# USB3_0.net
KiCad netlist of a schematic drawn in Altium Designer
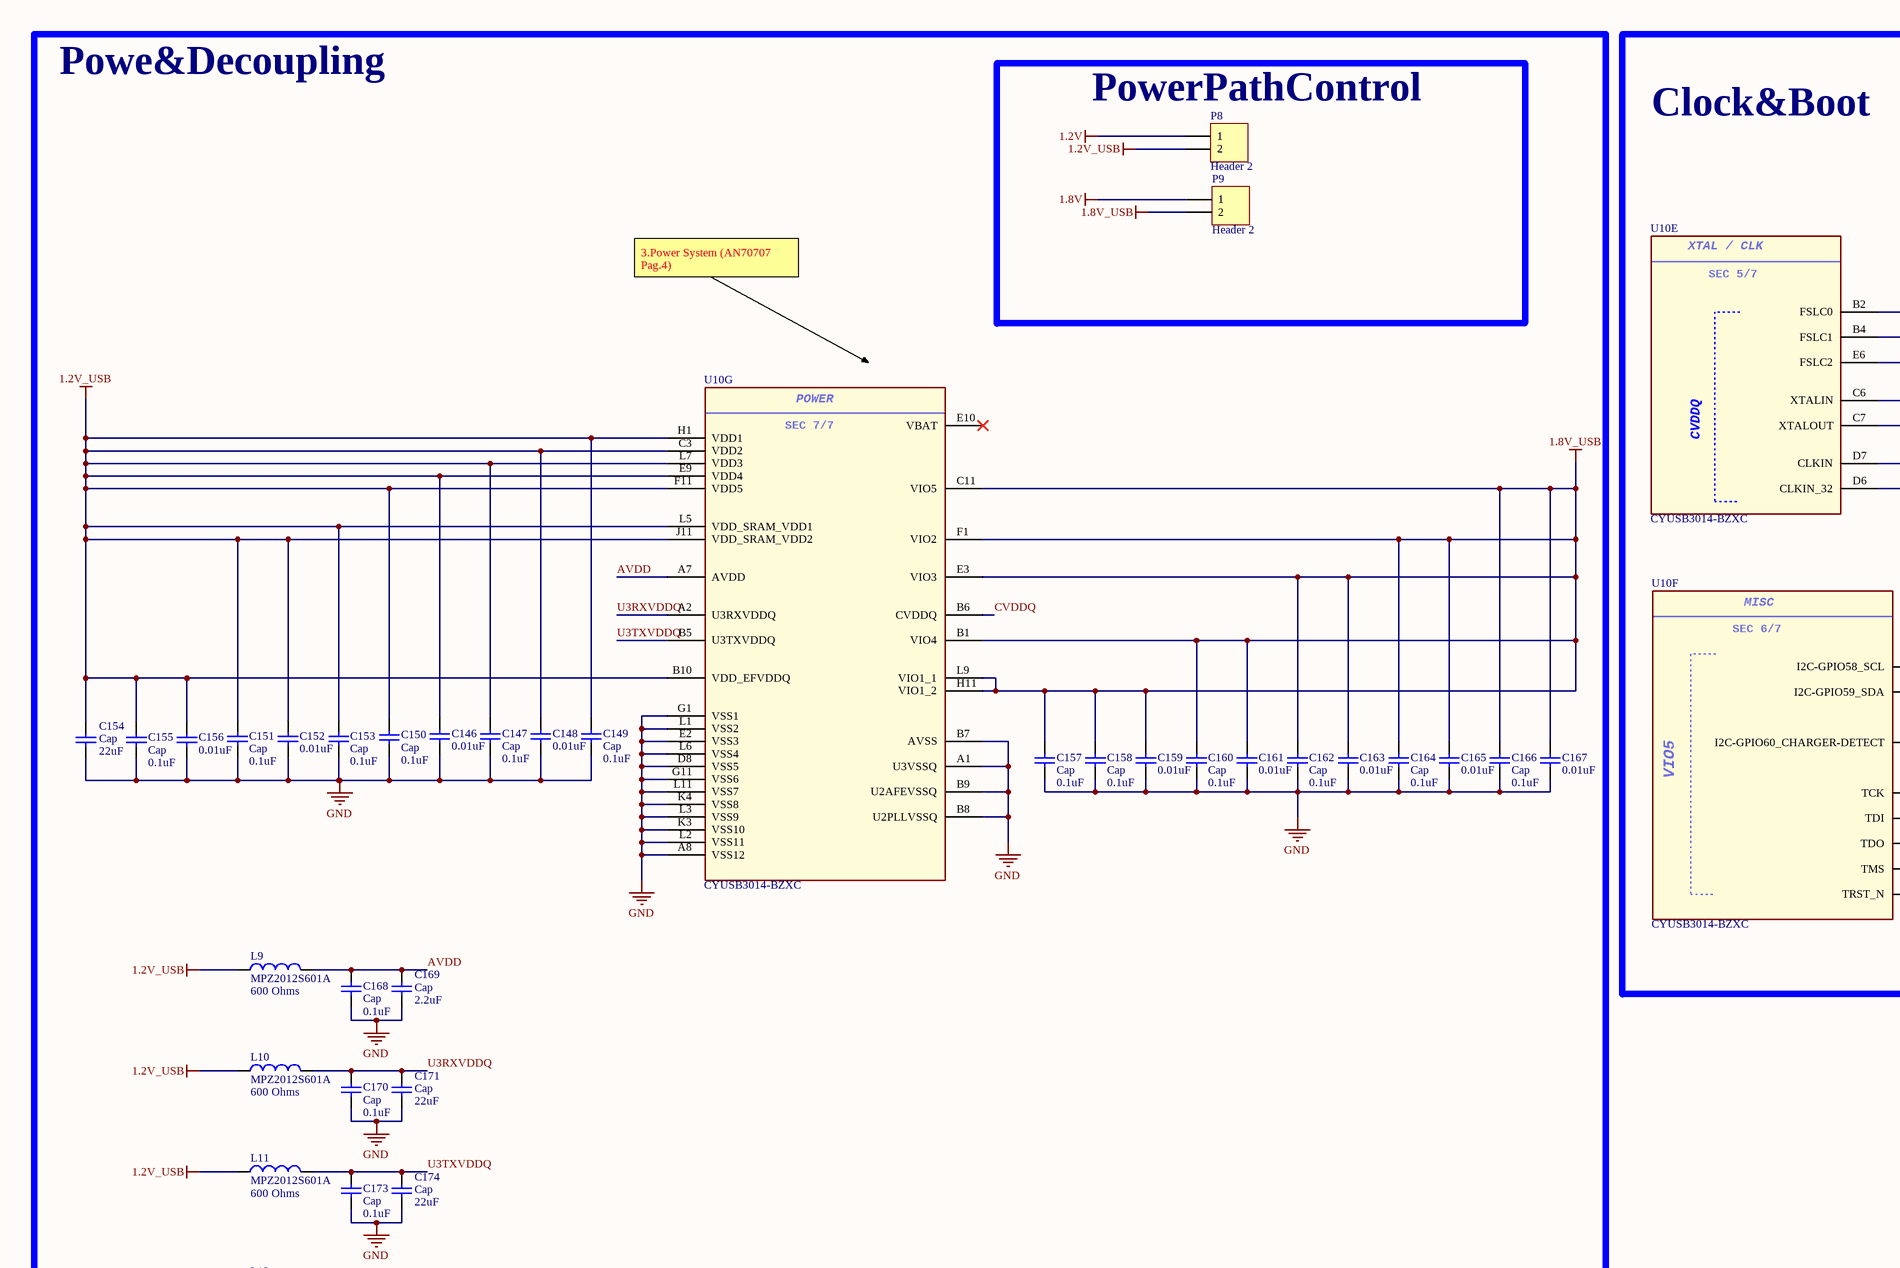
[diagram p0: USB3.0.SchDoc, top left]
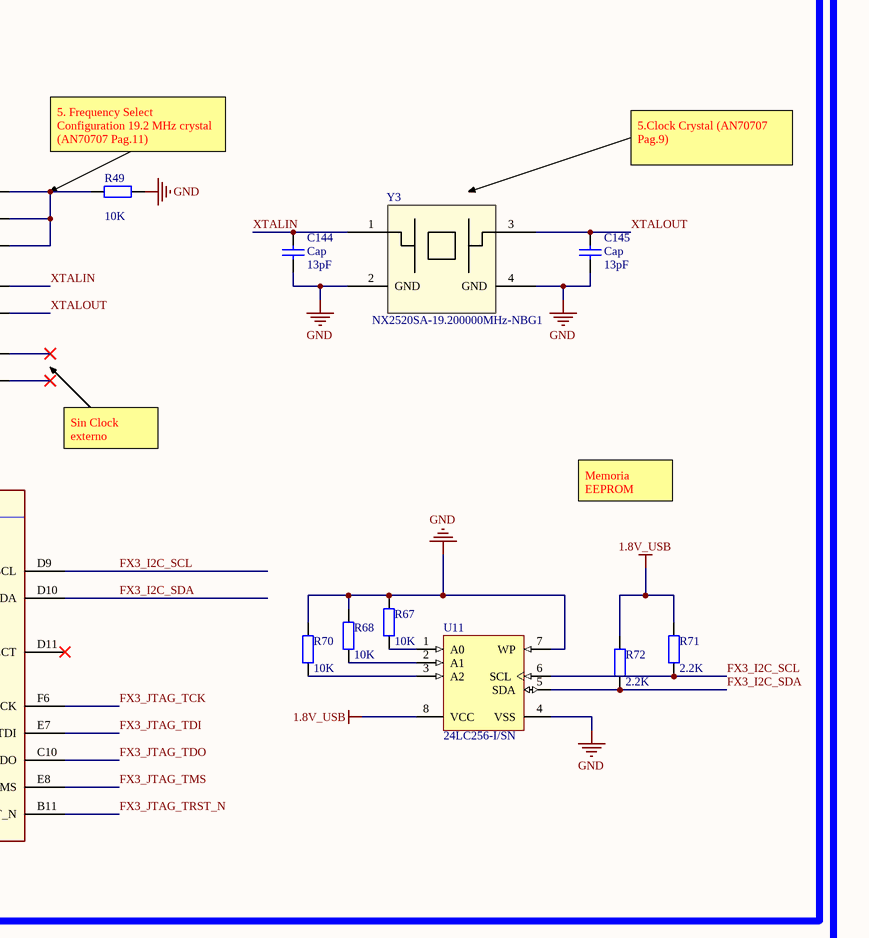
[diagram p1: USB3.0.SchDoc, top middle]
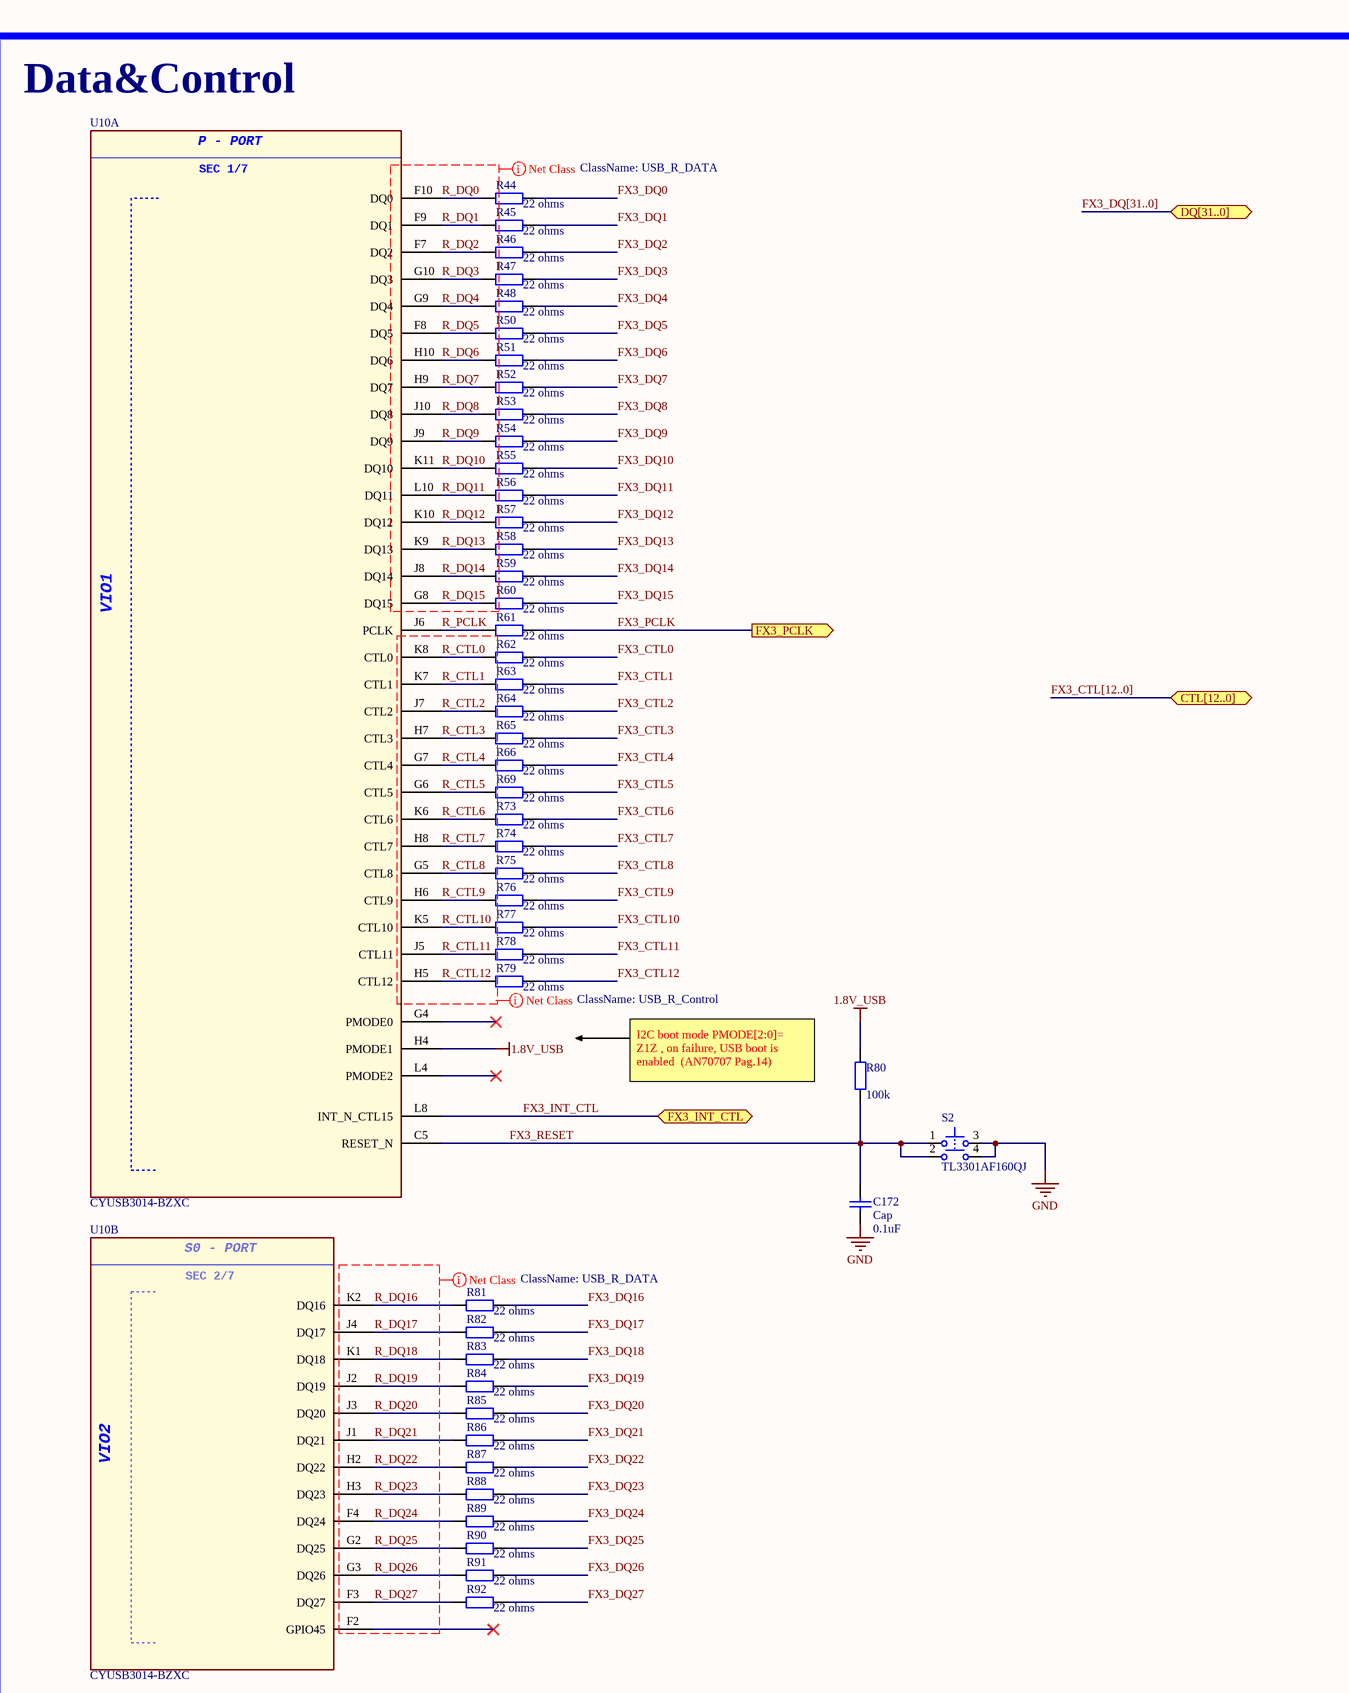
[diagram p2: USB3.0.SchDoc, top right]
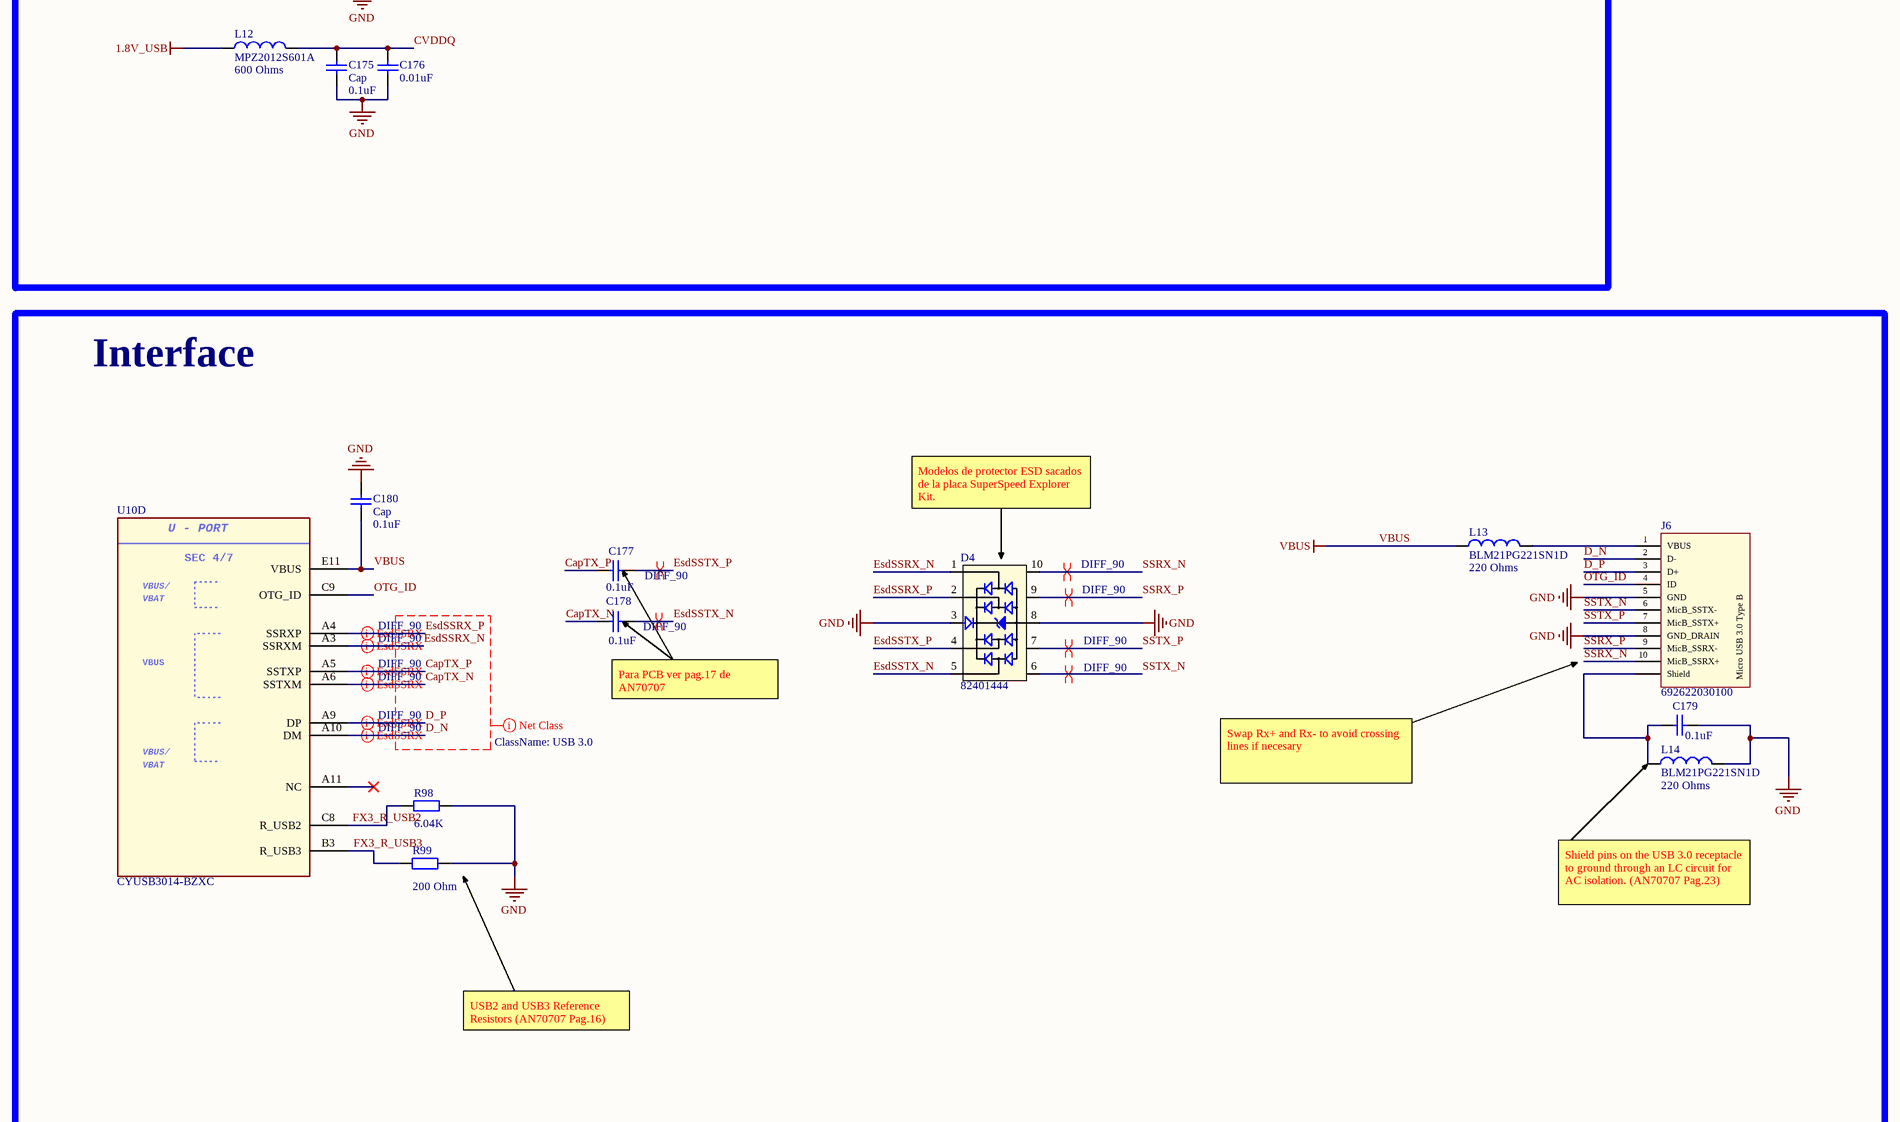
[diagram p3: USB3.0.SchDoc, bottom left]
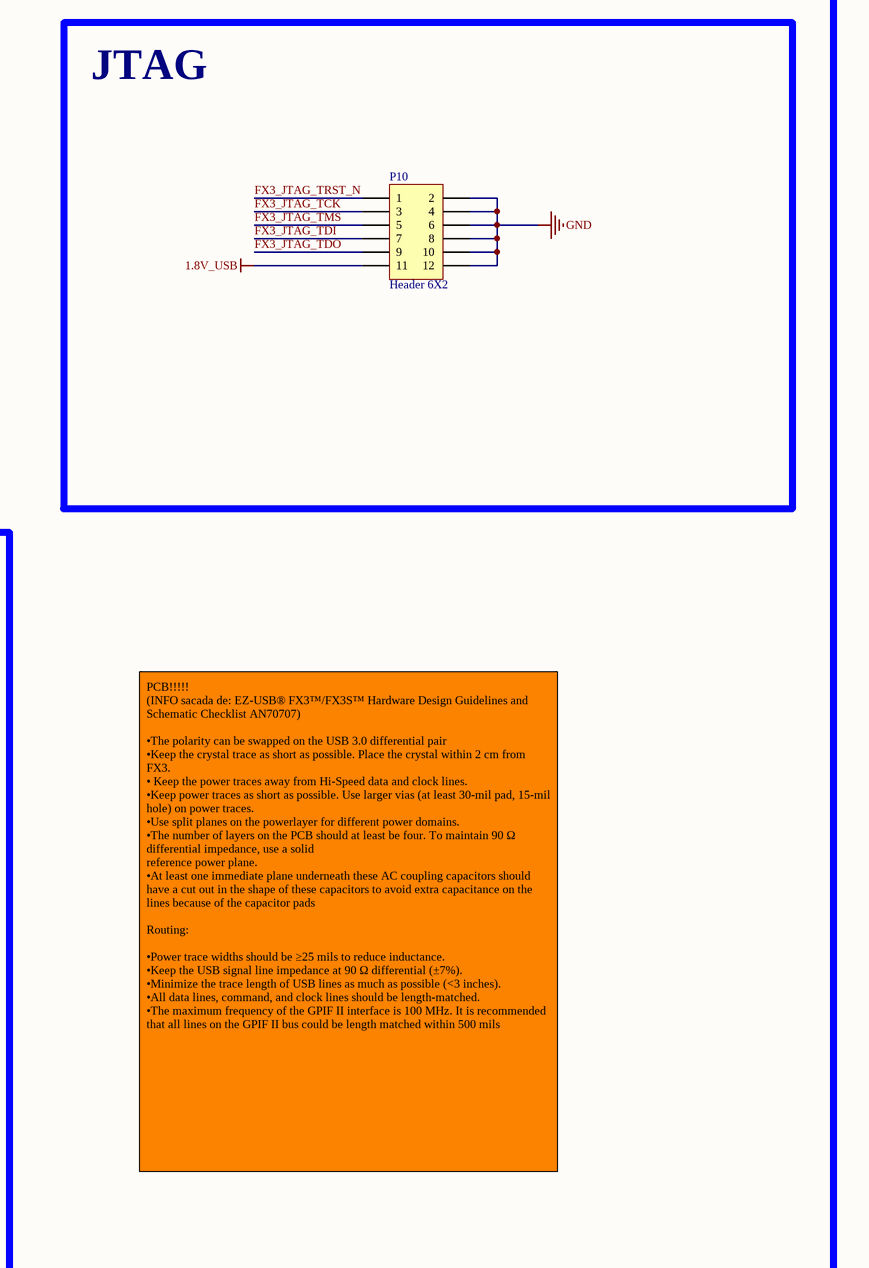
[diagram p4: USB3.0.SchDoc, bottom middle]
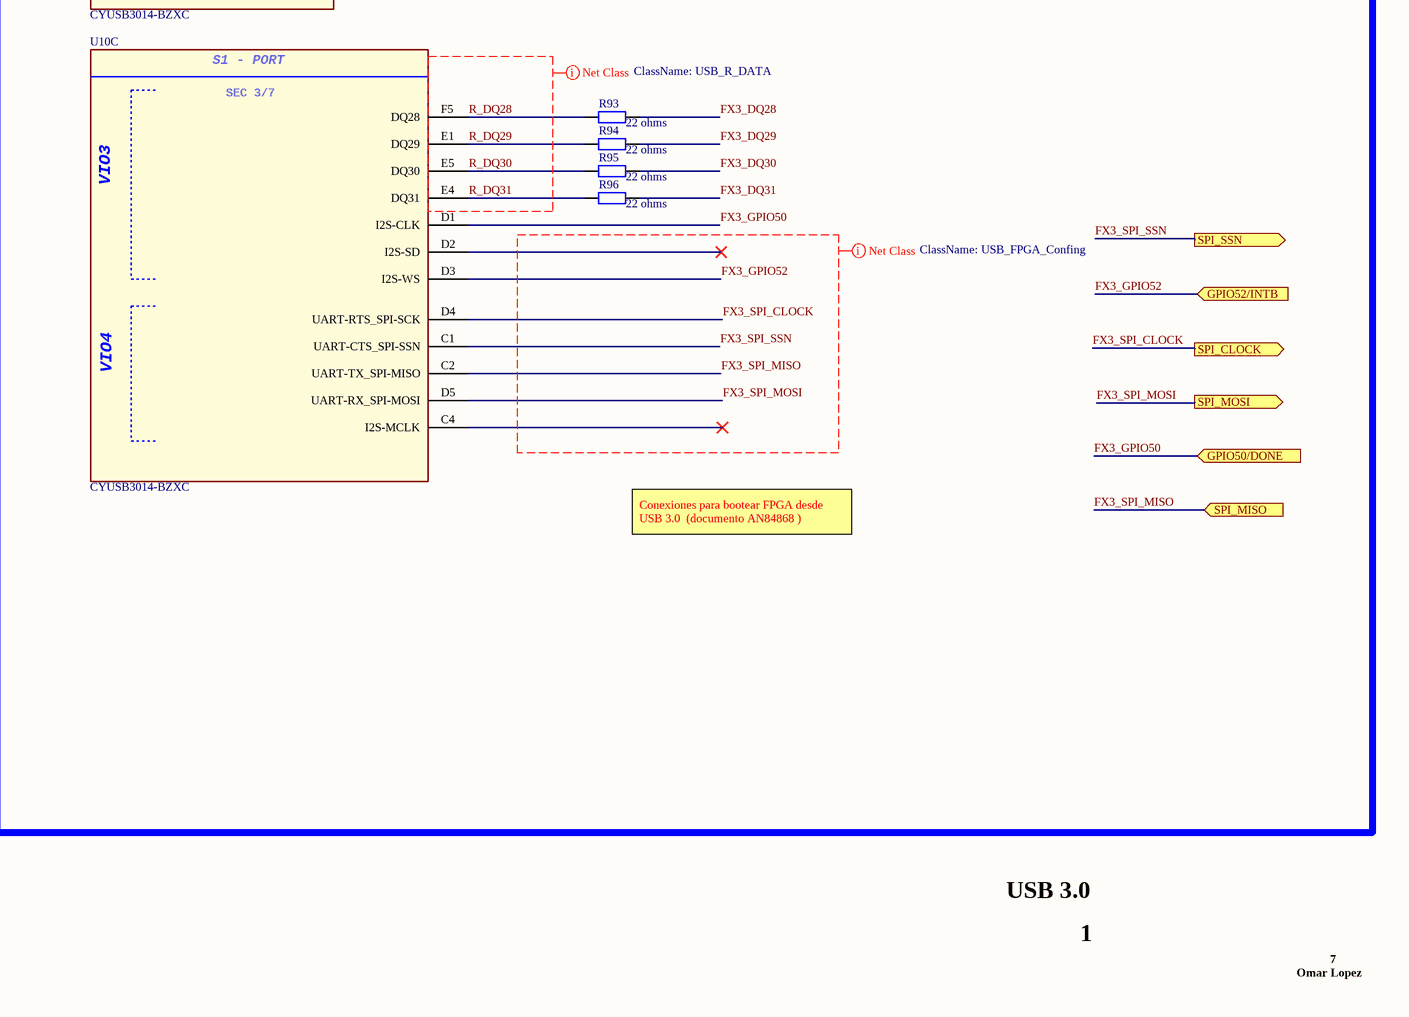
[diagram p5: USB3.0.SchDoc, bottom right]

(export (version "E")
  (design (tool "Eeschema 10.0.6"))
  (components
    (comp (ref "C144")
      (value "Cap")
      (footprint "MurataCapacitor:GRM0402MurataCap")
      (description "Capacitor")
      (fields
        (field (name "ALTIUM_VALUE") "13pF")
        (field (name "MANUFACTURER") "Murata")
        (field (name "TOLERANCE") "2%")
      )
      (libsource (lib "Miscellaneous Devices") (part "Cap"))
    )
    (comp (ref "C145")
      (value "Cap")
      (footprint "MurataCapacitor:GRM0402MurataCap")
      (description "Capacitor")
      (fields
        (field (name "ALTIUM_VALUE") "13pF")
        (field (name "MANUFACTURER") "Murata")
        (field (name "TOLERANCE") "2%")
      )
      (libsource (lib "Miscellaneous Devices") (part "Cap"))
    )
    (comp (ref "C146")
      (value "0.01uF")
      (footprint "MurataCapacitor:GRM0402MurataCap")
      (description "Capacitor")
      (fields (field (name "MANUFACTURER") "Murata") (field (name "TOLERANCE") "10%"))
      (libsource (lib "Miscellaneous Devices") (part "Cap"))
    )
    (comp (ref "C147")
      (value "Cap")
      (footprint "MurataCapacitor:GRM0402MurataCap")
      (description "Capacitor")
      (fields
        (field (name "ALTIUM_VALUE") "0.1uF")
        (field (name "MANUFACTURER") "Murata")
        (field (name "TOLERANCE") "10%")
      )
      (libsource (lib "Miscellaneous Devices") (part "Cap"))
    )
    (comp (ref "C148")
      (value "0.01uF")
      (footprint "MurataCapacitor:GRM0402MurataCap")
      (description "Capacitor")
      (fields (field (name "MANUFACTURER") "Murata") (field (name "TOLERANCE") "10%"))
      (libsource (lib "Miscellaneous Devices") (part "Cap"))
    )
    (comp (ref "C149")
      (value "Cap")
      (footprint "MurataCapacitor:GRM0402MurataCap")
      (description "Capacitor")
      (fields
        (field (name "ALTIUM_VALUE") "0.1uF")
        (field (name "MANUFACTURER") "Murata")
        (field (name "TOLERANCE") "10%")
      )
      (libsource (lib "Miscellaneous Devices") (part "Cap"))
    )
    (comp (ref "C150")
      (value "Cap")
      (footprint "MurataCapacitor:GRM0402MurataCap")
      (description "Capacitor")
      (fields
        (field (name "ALTIUM_VALUE") "0.1uF")
        (field (name "MANUFACTURER") "Murata")
        (field (name "TOLERANCE") "10%")
      )
      (libsource (lib "Miscellaneous Devices") (part "Cap"))
    )
    (comp (ref "C151")
      (value "Cap")
      (footprint "MurataCapacitor:GRM0402MurataCap")
      (description "Capacitor")
      (fields
        (field (name "ALTIUM_VALUE") "0.1uF")
        (field (name "MANUFACTURER") "Murata")
        (field (name "TOLERANCE") "10%")
      )
      (libsource (lib "Miscellaneous Devices") (part "Cap"))
    )
    (comp (ref "C152")
      (value "0.01uF")
      (footprint "MurataCapacitor:GRM0402MurataCap")
      (description "Capacitor")
      (fields (field (name "MANUFACTURER") "Murata") (field (name "TOLERANCE") "10%"))
      (libsource (lib "Miscellaneous Devices") (part "Cap"))
    )
    (comp (ref "C153")
      (value "Cap")
      (footprint "MurataCapacitor:GRM0402MurataCap")
      (description "Capacitor")
      (fields
        (field (name "ALTIUM_VALUE") "0.1uF")
        (field (name "MANUFACTURER") "Murata")
        (field (name "TOLERANCE") "10%")
      )
      (libsource (lib "Miscellaneous Devices") (part "Cap"))
    )
    (comp (ref "C154")
      (value "Cap")
      (footprint "MurataCapacitor:GRM0805MurataCap")
      (description "Capacitor")
      (fields
        (field (name "ALTIUM_VALUE") "22uF")
        (field (name "MANUFACTURER") "Murata")
        (field (name "TOLERANCE") "10%")
      )
      (libsource (lib "Miscellaneous Devices") (part "Cap"))
    )
    (comp (ref "C155")
      (value "Cap")
      (footprint "MurataCapacitor:GRM0402MurataCap")
      (description "Capacitor")
      (fields
        (field (name "ALTIUM_VALUE") "0.1uF")
        (field (name "MANUFACTURER") "Murata")
        (field (name "TOLERANCE") "10%")
      )
      (libsource (lib "Miscellaneous Devices") (part "Cap"))
    )
    (comp (ref "C156")
      (value "0.01uF")
      (footprint "MurataCapacitor:GRM0402MurataCap")
      (description "Capacitor")
      (fields (field (name "MANUFACTURER") "Murata") (field (name "TOLERANCE") "10%"))
      (libsource (lib "Miscellaneous Devices") (part "Cap"))
    )
    (comp (ref "C157")
      (value "Cap")
      (footprint "MurataCapacitor:GRM0402MurataCap")
      (description "Capacitor")
      (fields
        (field (name "ALTIUM_VALUE") "0.1uF")
        (field (name "MANUFACTURER") "Murata")
        (field (name "TOLERANCE") "10%")
      )
      (libsource (lib "Miscellaneous Devices") (part "Cap"))
    )
    (comp (ref "C158")
      (value "Cap")
      (footprint "MurataCapacitor:GRM0402MurataCap")
      (description "Capacitor")
      (fields
        (field (name "ALTIUM_VALUE") "0.1uF")
        (field (name "MANUFACTURER") "Murata")
        (field (name "TOLERANCE") "10%")
      )
      (libsource (lib "Miscellaneous Devices") (part "Cap"))
    )
    (comp (ref "C159")
      (value "0.01uF")
      (footprint "MurataCapacitor:GRM0402MurataCap")
      (description "Capacitor")
      (fields (field (name "MANUFACTURER") "Murata") (field (name "TOLERANCE") "10%"))
      (libsource (lib "Miscellaneous Devices") (part "Cap"))
    )
    (comp (ref "C160")
      (value "Cap")
      (footprint "MurataCapacitor:GRM0402MurataCap")
      (description "Capacitor")
      (fields
        (field (name "ALTIUM_VALUE") "0.1uF")
        (field (name "MANUFACTURER") "Murata")
        (field (name "TOLERANCE") "10%")
      )
      (libsource (lib "Miscellaneous Devices") (part "Cap"))
    )
    (comp (ref "C161")
      (value "0.01uF")
      (footprint "MurataCapacitor:GRM0402MurataCap")
      (description "Capacitor")
      (fields (field (name "MANUFACTURER") "Murata") (field (name "TOLERANCE") "10%"))
      (libsource (lib "Miscellaneous Devices") (part "Cap"))
    )
    (comp (ref "C162")
      (value "Cap")
      (footprint "MurataCapacitor:GRM0402MurataCap")
      (description "Capacitor")
      (fields
        (field (name "ALTIUM_VALUE") "0.1uF")
        (field (name "MANUFACTURER") "Murata")
        (field (name "TOLERANCE") "10%")
      )
      (libsource (lib "Miscellaneous Devices") (part "Cap"))
    )
    (comp (ref "C163")
      (value "0.01uF")
      (footprint "MurataCapacitor:GRM0402MurataCap")
      (description "Capacitor")
      (fields (field (name "MANUFACTURER") "Murata") (field (name "TOLERANCE") "10%"))
      (libsource (lib "Miscellaneous Devices") (part "Cap"))
    )
    (comp (ref "C164")
      (value "Cap")
      (footprint "MurataCapacitor:GRM0402MurataCap")
      (description "Capacitor")
      (fields
        (field (name "ALTIUM_VALUE") "0.1uF")
        (field (name "MANUFACTURER") "Murata")
        (field (name "TOLERANCE") "10%")
      )
      (libsource (lib "Miscellaneous Devices") (part "Cap"))
    )
    (comp (ref "C165")
      (value "0.01uF")
      (footprint "MurataCapacitor:GRM0402MurataCap")
      (description "Capacitor")
      (fields (field (name "MANUFACTURER") "Murata") (field (name "TOLERANCE") "10%"))
      (libsource (lib "Miscellaneous Devices") (part "Cap"))
    )
    (comp (ref "C166")
      (value "Cap")
      (footprint "MurataCapacitor:GRM0402MurataCap")
      (description "Capacitor")
      (fields
        (field (name "ALTIUM_VALUE") "0.1uF")
        (field (name "MANUFACTURER") "Murata")
        (field (name "TOLERANCE") "10%")
      )
      (libsource (lib "Miscellaneous Devices") (part "Cap"))
    )
    (comp (ref "C167")
      (value "0.01uF")
      (footprint "MurataCapacitor:GRM0402MurataCap")
      (description "Capacitor")
      (fields (field (name "MANUFACTURER") "Murata") (field (name "TOLERANCE") "10%"))
      (libsource (lib "Miscellaneous Devices") (part "Cap"))
    )
    (comp (ref "C168")
      (value "Cap")
      (footprint "MurataCapacitor:GRM0402MurataCap")
      (description "Capacitor")
      (fields
        (field (name "ALTIUM_VALUE") "0.1uF")
        (field (name "MANUFACTURER") "Murata")
        (field (name "TOLERANCE") "10%")
      )
      (libsource (lib "Miscellaneous Devices") (part "Cap"))
    )
    (comp (ref "C169")
      (value "Cap")
      (footprint "MurataCapacitor:GRM0402MurataCap")
      (description "Capacitor")
      (fields
        (field (name "ALTIUM_VALUE") "2.2uF")
        (field (name "MANUFACTURER") "Murata")
        (field (name "TOLERANCE") "10%")
      )
      (libsource (lib "Miscellaneous Devices") (part "Cap"))
    )
    (comp (ref "C170")
      (value "Cap")
      (footprint "MurataCapacitor:GRM0402MurataCap")
      (description "Capacitor")
      (fields
        (field (name "ALTIUM_VALUE") "0.1uF")
        (field (name "MANUFACTURER") "Murata")
        (field (name "TOLERANCE") "10%")
      )
      (libsource (lib "Miscellaneous Devices") (part "Cap"))
    )
    (comp (ref "C171")
      (value "Cap")
      (footprint "MurataCapacitor:GRM0805MurataCap")
      (description "Capacitor")
      (fields
        (field (name "ALTIUM_VALUE") "22uF")
        (field (name "MANUFACTURER") "Murata")
        (field (name "TOLERANCE") "10%")
      )
      (libsource (lib "Miscellaneous Devices") (part "Cap"))
    )
    (comp (ref "C172")
      (value "Cap")
      (footprint "MurataCapacitor:GRM0402MurataCap")
      (description "Capacitor")
      (fields
        (field (name "ALTIUM_VALUE") "0.1uF")
        (field (name "MANUFACTURER") "Murata")
        (field (name "TOLERANCE") "10%")
      )
      (libsource (lib "Miscellaneous Devices") (part "Cap"))
    )
    (comp (ref "C173")
      (value "Cap")
      (footprint "MurataCapacitor:GRM0402MurataCap")
      (description "Capacitor")
      (fields
        (field (name "ALTIUM_VALUE") "0.1uF")
        (field (name "MANUFACTURER") "Murata")
        (field (name "TOLERANCE") "10%")
      )
      (libsource (lib "Miscellaneous Devices") (part "Cap"))
    )
    (comp (ref "C174")
      (value "Cap")
      (footprint "MurataCapacitor:GRM0805MurataCap")
      (description "Capacitor")
      (fields
        (field (name "ALTIUM_VALUE") "22uF")
        (field (name "MANUFACTURER") "Murata")
        (field (name "TOLERANCE") "10%")
      )
      (libsource (lib "Miscellaneous Devices") (part "Cap"))
    )
    (comp (ref "C175")
      (value "Cap")
      (footprint "MurataCapacitor:GRM0402MurataCap")
      (description "Capacitor")
      (fields
        (field (name "ALTIUM_VALUE") "0.1uF")
        (field (name "MANUFACTURER") "Murata")
        (field (name "TOLERANCE") "10%")
      )
      (libsource (lib "Miscellaneous Devices") (part "Cap"))
    )
    (comp (ref "C176")
      (value "0.01uF")
      (footprint "MurataCapacitor:GRM0402MurataCap")
      (description "Capacitor")
      (fields (field (name "MANUFACTURER") "Murata") (field (name "TOLERANCE") "10%"))
      (libsource (lib "Miscellaneous Devices") (part "Cap"))
    )
    (comp (ref "C177")
      (value "0.1uF")
      (footprint "MurataCapacitor:GRM0402MurataCap")
      (description "Capacitor")
      (fields (field (name "MANUFACTURER") "Murata") (field (name "TOLERANCE") "10%"))
      (libsource (lib "Miscellaneous Devices") (part "Cap"))
    )
    (comp (ref "C178")
      (value "0.1uF")
      (footprint "MurataCapacitor:GRM0402MurataCap")
      (description "Capacitor")
      (fields (field (name "MANUFACTURER") "Murata") (field (name "TOLERANCE") "10%"))
      (libsource (lib "Miscellaneous Devices") (part "Cap"))
    )
    (comp (ref "C179")
      (value "0.1uF")
      (footprint "MurataCapacitor:GRM0402MurataCap")
      (description "Capacitor")
      (fields (field (name "MANUFACTURER") "Murata") (field (name "TOLERANCE") "10%"))
      (libsource (lib "Miscellaneous Devices") (part "Cap"))
    )
    (comp (ref "C180")
      (value "Cap")
      (footprint "MurataCapacitor:GRM0402MurataCap")
      (description "Capacitor")
      (fields
        (field (name "ALTIUM_VALUE") "0.1uF")
        (field (name "MANUFACTURER") "Murata")
        (field (name "TOLERANCE") "10%")
      )
      (libsource (lib "Miscellaneous Devices") (part "Cap"))
    )
    (comp (ref "D4")
      (value "82401444")
      (footprint "WE-TVS-SUPER SPEED:MSOP-10L")
      (description "TVS Diode WE-TVS-SS, VRWM=5V")
      (fields (field (name "MANUFACTURER") "Würth Elektronik eiSos GmbH"))
      (libsource (lib "ALTIUM-WE-TVS-HS-rev16a") (part "WE-TVS-SS,MSOP-10L, 82401444"))
    )
    (comp (ref "J6")
      (value "692622030100")
      (footprint "USB Connectors:692622030100")
      (description "Micro USB 3.0 Type B Horizontal SMT WR-COM")
      (libsource (lib "ALTIUM-WR-COM-rev17a") (part "692622030100"))
    )
    (comp (ref "L9")
      (value "MPZ2012S601A")
      (footprint "MPZSeries:MPZ2012")
      (description "Inductor")
      (fields (field (name "ALTIUM_VALUE") "600 Ohms") (field (name "MANUFACTURER") "TDK"))
      (libsource (lib "Miscellaneous Devices") (part "Inductor"))
    )
    (comp (ref "L10")
      (value "MPZ2012S601A")
      (footprint "MPZSeries:MPZ2012")
      (description "Inductor")
      (fields (field (name "ALTIUM_VALUE") "600 Ohms") (field (name "MANUFACTURER") "TDK"))
      (libsource (lib "Miscellaneous Devices") (part "Inductor"))
    )
    (comp (ref "L11")
      (value "MPZ2012S601A")
      (footprint "MPZSeries:MPZ2012")
      (description "Inductor")
      (fields (field (name "ALTIUM_VALUE") "600 Ohms") (field (name "MANUFACTURER") "TDK"))
      (libsource (lib "Miscellaneous Devices") (part "Inductor"))
    )
    (comp (ref "L12")
      (value "MPZ2012S601A")
      (footprint "MPZSeries:MPZ2012")
      (description "Inductor")
      (fields (field (name "ALTIUM_VALUE") "600 Ohms") (field (name "MANUFACTURER") "TDK"))
      (libsource (lib "Miscellaneous Devices") (part "Inductor"))
    )
    (comp (ref "L13")
      (value "BLM21PG221SN1D")
      (footprint "BLMSeries:BLM21")
      (description "Inductor")
      (fields
        (field (name "ALTIUM_VALUE") "220 Ohms")
        (field (name "MANUFACTURER") "Murata")
        (field (name "TOLERANCE") "25%")
      )
      (libsource (lib "Miscellaneous Devices") (part "Inductor"))
    )
    (comp (ref "L14")
      (value "BLM21PG221SN1D")
      (footprint "BLMSeries:BLM21")
      (description "Inductor")
      (fields
        (field (name "ALTIUM_VALUE") "220 Ohms")
        (field (name "MANUFACTURER") "Murata")
        (field (name "TOLERANCE") "25%")
      )
      (libsource (lib "Miscellaneous Devices") (part "Inductor"))
    )
    (comp (ref "P8")
      (value "Header 2")
      (footprint "Header2x1")
      (description "Header, 2-Pin")
      (fields (field (name "MANUFACTURER") "TE Connectivity") (field (name "PARTNUMBER") "826629"))
      (libsource (lib "Miscellaneous Connectors") (part "Header 2"))
    )
    (comp (ref "P9")
      (value "Header 2")
      (footprint "Header2x1")
      (description "Header, 2-Pin")
      (fields (field (name "MANUFACTURER") "TE Connectivity") (field (name "PARTNUMBER") "826629"))
      (libsource (lib "Miscellaneous Connectors") (part "Header 2"))
    )
    (comp (ref "P10")
      (value "Header 6X2")
      (footprint "HDR2X6")
      (description "Header, 6-Pin, Dual row")
      (libsource (lib "Miscellaneous Connectors") (part "Header 6X2"))
    )
    (comp (ref "R44")
      (value "22 ohms")
      (footprint "Res0402ERJ:RC0402N")
      (description "Resistor")
      (fields (field (name "MANUFACTURER") "Panasonic") (field (name "TOLERANCE") "1%"))
      (libsource (lib "Miscellaneous Devices") (part "Res2"))
    )
    (comp (ref "R45")
      (value "22 ohms")
      (footprint "Res0402ERJ:RC0402N")
      (description "Resistor")
      (fields (field (name "MANUFACTURER") "Panasonic") (field (name "TOLERANCE") "1%"))
      (libsource (lib "Miscellaneous Devices") (part "Res2"))
    )
    (comp (ref "R46")
      (value "22 ohms")
      (footprint "Res0402ERJ:RC0402N")
      (description "Resistor")
      (fields (field (name "MANUFACTURER") "Panasonic") (field (name "TOLERANCE") "1%"))
      (libsource (lib "Miscellaneous Devices") (part "Res2"))
    )
    (comp (ref "R47")
      (value "22 ohms")
      (footprint "Res0402ERJ:RC0402N")
      (description "Resistor")
      (fields (field (name "MANUFACTURER") "Panasonic") (field (name "TOLERANCE") "1%"))
      (libsource (lib "Miscellaneous Devices") (part "Res2"))
    )
    (comp (ref "R48")
      (value "22 ohms")
      (footprint "Res0402ERJ:RC0402N")
      (description "Resistor")
      (fields (field (name "MANUFACTURER") "Panasonic") (field (name "TOLERANCE") "1%"))
      (libsource (lib "Miscellaneous Devices") (part "Res2"))
    )
    (comp (ref "R49")
      (value "10K")
      (footprint "Res0402ERJ:RC0402N")
      (description "Resistor")
      (fields (field (name "MANUFACTURER") "Panasonic") (field (name "TOLERANCE") "1%"))
      (libsource (lib "") (part "Res2_1"))
    )
    (comp (ref "R50")
      (value "22 ohms")
      (footprint "Res0402ERJ:RC0402N")
      (description "Resistor")
      (fields (field (name "MANUFACTURER") "Panasonic") (field (name "TOLERANCE") "1%"))
      (libsource (lib "Miscellaneous Devices") (part "Res2"))
    )
    (comp (ref "R51")
      (value "22 ohms")
      (footprint "Res0402ERJ:RC0402N")
      (description "Resistor")
      (fields (field (name "MANUFACTURER") "Panasonic") (field (name "TOLERANCE") "1%"))
      (libsource (lib "Miscellaneous Devices") (part "Res2"))
    )
    (comp (ref "R52")
      (value "22 ohms")
      (footprint "Res0402ERJ:RC0402N")
      (description "Resistor")
      (fields (field (name "MANUFACTURER") "Panasonic") (field (name "TOLERANCE") "1%"))
      (libsource (lib "Miscellaneous Devices") (part "Res2"))
    )
    (comp (ref "R53")
      (value "22 ohms")
      (footprint "Res0402ERJ:RC0402N")
      (description "Resistor")
      (fields (field (name "MANUFACTURER") "Panasonic") (field (name "TOLERANCE") "1%"))
      (libsource (lib "Miscellaneous Devices") (part "Res2"))
    )
    (comp (ref "R54")
      (value "22 ohms")
      (footprint "Res0402ERJ:RC0402N")
      (description "Resistor")
      (fields (field (name "MANUFACTURER") "Panasonic") (field (name "TOLERANCE") "1%"))
      (libsource (lib "Miscellaneous Devices") (part "Res2"))
    )
    (comp (ref "R55")
      (value "22 ohms")
      (footprint "Res0402ERJ:RC0402N")
      (description "Resistor")
      (fields (field (name "MANUFACTURER") "Panasonic") (field (name "TOLERANCE") "1%"))
      (libsource (lib "Miscellaneous Devices") (part "Res2"))
    )
    (comp (ref "R56")
      (value "22 ohms")
      (footprint "Res0402ERJ:RC0402N")
      (description "Resistor")
      (fields (field (name "MANUFACTURER") "Panasonic") (field (name "TOLERANCE") "1%"))
      (libsource (lib "Miscellaneous Devices") (part "Res2"))
    )
    (comp (ref "R57")
      (value "22 ohms")
      (footprint "Res0402ERJ:RC0402N")
      (description "Resistor")
      (fields (field (name "MANUFACTURER") "Panasonic") (field (name "TOLERANCE") "1%"))
      (libsource (lib "Miscellaneous Devices") (part "Res2"))
    )
    (comp (ref "R58")
      (value "22 ohms")
      (footprint "Res0402ERJ:RC0402N")
      (description "Resistor")
      (fields (field (name "MANUFACTURER") "Panasonic") (field (name "TOLERANCE") "1%"))
      (libsource (lib "Miscellaneous Devices") (part "Res2"))
    )
    (comp (ref "R59")
      (value "22 ohms")
      (footprint "Res0402ERJ:RC0402N")
      (description "Resistor")
      (fields (field (name "MANUFACTURER") "Panasonic") (field (name "TOLERANCE") "1%"))
      (libsource (lib "Miscellaneous Devices") (part "Res2"))
    )
    (comp (ref "R60")
      (value "22 ohms")
      (footprint "Res0402ERJ:RC0402N")
      (description "Resistor")
      (fields (field (name "MANUFACTURER") "Panasonic") (field (name "TOLERANCE") "1%"))
      (libsource (lib "Miscellaneous Devices") (part "Res2"))
    )
    (comp (ref "R61")
      (value "22 ohms")
      (footprint "Res0402ERJ:RC0402N")
      (description "Resistor")
      (fields (field (name "MANUFACTURER") "Panasonic") (field (name "TOLERANCE") "1%"))
      (libsource (lib "Miscellaneous Devices") (part "Res2"))
    )
    (comp (ref "R62")
      (value "22 ohms")
      (footprint "Res0402ERJ:RC0402N")
      (description "Resistor")
      (fields (field (name "MANUFACTURER") "Panasonic") (field (name "TOLERANCE") "1%"))
      (libsource (lib "Miscellaneous Devices") (part "Res2"))
    )
    (comp (ref "R63")
      (value "22 ohms")
      (footprint "Res0402ERJ:RC0402N")
      (description "Resistor")
      (fields (field (name "MANUFACTURER") "Panasonic") (field (name "TOLERANCE") "1%"))
      (libsource (lib "Miscellaneous Devices") (part "Res2"))
    )
    (comp (ref "R64")
      (value "22 ohms")
      (footprint "Res0402ERJ:RC0402N")
      (description "Resistor")
      (fields (field (name "MANUFACTURER") "Panasonic") (field (name "TOLERANCE") "1%"))
      (libsource (lib "Miscellaneous Devices") (part "Res2"))
    )
    (comp (ref "R65")
      (value "22 ohms")
      (footprint "Res0402ERJ:RC0402N")
      (description "Resistor")
      (fields (field (name "MANUFACTURER") "Panasonic") (field (name "TOLERANCE") "1%"))
      (libsource (lib "Miscellaneous Devices") (part "Res2"))
    )
    (comp (ref "R66")
      (value "22 ohms")
      (footprint "Res0402ERJ:RC0402N")
      (description "Resistor")
      (fields (field (name "MANUFACTURER") "Panasonic") (field (name "TOLERANCE") "1%"))
      (libsource (lib "Miscellaneous Devices") (part "Res2"))
    )
    (comp (ref "R67")
      (value "10K")
      (footprint "Res0402ERJ:RC0402N")
      (description "Resistor")
      (fields (field (name "MANUFACTURER") "Panasonic") (field (name "TOLERANCE") "1%"))
      (libsource (lib "") (part "Res2_3"))
    )
    (comp (ref "R68")
      (value "10K")
      (footprint "Res0402ERJ:RC0402N")
      (description "Resistor")
      (fields (field (name "MANUFACTURER") "Panasonic") (field (name "TOLERANCE") "1%"))
      (libsource (lib "") (part "Res2_3"))
    )
    (comp (ref "R69")
      (value "22 ohms")
      (footprint "Res0402ERJ:RC0402N")
      (description "Resistor")
      (fields (field (name "MANUFACTURER") "Panasonic") (field (name "TOLERANCE") "1%"))
      (libsource (lib "Miscellaneous Devices") (part "Res2"))
    )
    (comp (ref "R70")
      (value "10K")
      (footprint "Res0402ERJ:RC0402N")
      (description "Resistor")
      (fields (field (name "MANUFACTURER") "Panasonic") (field (name "TOLERANCE") "1%"))
      (libsource (lib "") (part "Res2_3"))
    )
    (comp (ref "R71")
      (value "2.2K")
      (footprint "Res0402ERJ:RC0402N")
      (description "Resistor")
      (fields (field (name "MANUFACTURER") "Panasonic") (field (name "TOLERANCE") "1%"))
      (libsource (lib "") (part "Res2_2"))
    )
    (comp (ref "R72")
      (value "2.2K")
      (footprint "Res0402ERJ:RC0402N")
      (description "Resistor")
      (fields (field (name "MANUFACTURER") "Panasonic") (field (name "TOLERANCE") "1%"))
      (libsource (lib "") (part "Res2_2"))
    )
    (comp (ref "R73")
      (value "22 ohms")
      (footprint "Res0402ERJ:RC0402N")
      (description "Resistor")
      (fields (field (name "MANUFACTURER") "Panasonic") (field (name "TOLERANCE") "1%"))
      (libsource (lib "Miscellaneous Devices") (part "Res2"))
    )
    (comp (ref "R74")
      (value "22 ohms")
      (footprint "Res0402ERJ:RC0402N")
      (description "Resistor")
      (fields (field (name "MANUFACTURER") "Panasonic") (field (name "TOLERANCE") "1%"))
      (libsource (lib "Miscellaneous Devices") (part "Res2"))
    )
    (comp (ref "R75")
      (value "22 ohms")
      (footprint "Res0402ERJ:RC0402N")
      (description "Resistor")
      (fields (field (name "MANUFACTURER") "Panasonic") (field (name "TOLERANCE") "1%"))
      (libsource (lib "Miscellaneous Devices") (part "Res2"))
    )
    (comp (ref "R76")
      (value "22 ohms")
      (footprint "Res0402ERJ:RC0402N")
      (description "Resistor")
      (fields (field (name "MANUFACTURER") "Panasonic") (field (name "TOLERANCE") "1%"))
      (libsource (lib "Miscellaneous Devices") (part "Res2"))
    )
    (comp (ref "R77")
      (value "22 ohms")
      (footprint "Res0402ERJ:RC0402N")
      (description "Resistor")
      (fields (field (name "MANUFACTURER") "Panasonic") (field (name "TOLERANCE") "1%"))
      (libsource (lib "Miscellaneous Devices") (part "Res2"))
    )
    (comp (ref "R78")
      (value "22 ohms")
      (footprint "Res0402ERJ:RC0402N")
      (description "Resistor")
      (fields (field (name "MANUFACTURER") "Panasonic") (field (name "TOLERANCE") "1%"))
      (libsource (lib "Miscellaneous Devices") (part "Res2"))
    )
    (comp (ref "R79")
      (value "22 ohms")
      (footprint "Res0402ERJ:RC0402N")
      (description "Resistor")
      (fields (field (name "MANUFACTURER") "Panasonic") (field (name "TOLERANCE") "1%"))
      (libsource (lib "Miscellaneous Devices") (part "Res2"))
    )
    (comp (ref "R80")
      (value "100k")
      (footprint "Res0402ERJ:RC0402N")
      (description "Resistor")
      (fields (field (name "MANUFACTURER") "Panasonic") (field (name "TOLERANCE") "1%"))
      (libsource (lib "") (part "Res2_3"))
    )
    (comp (ref "R81")
      (value "22 ohms")
      (footprint "Res0402ERJ:RC0402N")
      (description "Resistor")
      (fields (field (name "MANUFACTURER") "Panasonic") (field (name "TOLERANCE") "1%"))
      (libsource (lib "Miscellaneous Devices") (part "Res2"))
    )
    (comp (ref "R82")
      (value "22 ohms")
      (footprint "Res0402ERJ:RC0402N")
      (description "Resistor")
      (fields (field (name "MANUFACTURER") "Panasonic") (field (name "TOLERANCE") "1%"))
      (libsource (lib "Miscellaneous Devices") (part "Res2"))
    )
    (comp (ref "R83")
      (value "22 ohms")
      (footprint "Res0402ERJ:RC0402N")
      (description "Resistor")
      (fields (field (name "MANUFACTURER") "Panasonic") (field (name "TOLERANCE") "1%"))
      (libsource (lib "Miscellaneous Devices") (part "Res2"))
    )
    (comp (ref "R84")
      (value "22 ohms")
      (footprint "Res0402ERJ:RC0402N")
      (description "Resistor")
      (fields (field (name "MANUFACTURER") "Panasonic") (field (name "TOLERANCE") "1%"))
      (libsource (lib "Miscellaneous Devices") (part "Res2"))
    )
    (comp (ref "R85")
      (value "22 ohms")
      (footprint "Res0402ERJ:RC0402N")
      (description "Resistor")
      (fields (field (name "MANUFACTURER") "Panasonic") (field (name "TOLERANCE") "1%"))
      (libsource (lib "Miscellaneous Devices") (part "Res2"))
    )
    (comp (ref "R86")
      (value "22 ohms")
      (footprint "Res0402ERJ:RC0402N")
      (description "Resistor")
      (fields (field (name "MANUFACTURER") "Panasonic") (field (name "TOLERANCE") "1%"))
      (libsource (lib "Miscellaneous Devices") (part "Res2"))
    )
    (comp (ref "R87")
      (value "22 ohms")
      (footprint "Res0402ERJ:RC0402N")
      (description "Resistor")
      (fields (field (name "MANUFACTURER") "Panasonic") (field (name "TOLERANCE") "1%"))
      (libsource (lib "Miscellaneous Devices") (part "Res2"))
    )
    (comp (ref "R88")
      (value "22 ohms")
      (footprint "Res0402ERJ:RC0402N")
      (description "Resistor")
      (fields (field (name "MANUFACTURER") "Panasonic") (field (name "TOLERANCE") "1%"))
      (libsource (lib "Miscellaneous Devices") (part "Res2"))
    )
    (comp (ref "R89")
      (value "22 ohms")
      (footprint "Res0402ERJ:RC0402N")
      (description "Resistor")
      (fields (field (name "MANUFACTURER") "Panasonic") (field (name "TOLERANCE") "1%"))
      (libsource (lib "Miscellaneous Devices") (part "Res2"))
    )
    (comp (ref "R90")
      (value "22 ohms")
      (footprint "Res0402ERJ:RC0402N")
      (description "Resistor")
      (fields (field (name "MANUFACTURER") "Panasonic") (field (name "TOLERANCE") "1%"))
      (libsource (lib "Miscellaneous Devices") (part "Res2"))
    )
    (comp (ref "R91")
      (value "22 ohms")
      (footprint "Res0402ERJ:RC0402N")
      (description "Resistor")
      (fields (field (name "MANUFACTURER") "Panasonic") (field (name "TOLERANCE") "1%"))
      (libsource (lib "Miscellaneous Devices") (part "Res2"))
    )
    (comp (ref "R92")
      (value "22 ohms")
      (footprint "Res0402ERJ:RC0402N")
      (description "Resistor")
      (fields (field (name "MANUFACTURER") "Panasonic") (field (name "TOLERANCE") "1%"))
      (libsource (lib "Miscellaneous Devices") (part "Res2"))
    )
    (comp (ref "R93")
      (value "22 ohms")
      (footprint "Res0402ERJ:RC0402N")
      (description "Resistor")
      (fields (field (name "MANUFACTURER") "Panasonic") (field (name "TOLERANCE") "1%"))
      (libsource (lib "Miscellaneous Devices") (part "Res2"))
    )
    (comp (ref "R94")
      (value "22 ohms")
      (footprint "Res0402ERJ:RC0402N")
      (description "Resistor")
      (fields (field (name "MANUFACTURER") "Panasonic") (field (name "TOLERANCE") "1%"))
      (libsource (lib "Miscellaneous Devices") (part "Res2"))
    )
    (comp (ref "R95")
      (value "22 ohms")
      (footprint "Res0402ERJ:RC0402N")
      (description "Resistor")
      (fields (field (name "MANUFACTURER") "Panasonic") (field (name "TOLERANCE") "1%"))
      (libsource (lib "Miscellaneous Devices") (part "Res2"))
    )
    (comp (ref "R96")
      (value "22 ohms")
      (footprint "Res0402ERJ:RC0402N")
      (description "Resistor")
      (fields (field (name "MANUFACTURER") "Panasonic") (field (name "TOLERANCE") "1%"))
      (libsource (lib "Miscellaneous Devices") (part "Res2"))
    )
    (comp (ref "R98")
      (value "6.04K")
      (footprint "Res0402ERJ:RC0402N")
      (description "Resistor")
      (fields (field (name "MANUFACTURER") "Panasonic") (field (name "TOLERANCE") "1%"))
      (libsource (lib "Miscellaneous Devices") (part "Res2"))
    )
    (comp (ref "R99")
      (value "200 Ohm")
      (footprint "Res0402ERJ:RC0402N")
      (description "Resistor")
      (fields (field (name "MANUFACTURER") "Panasonic") (field (name "TOLERANCE") "1%"))
      (libsource (lib "Miscellaneous Devices") (part "Res2"))
    )
    (comp (ref "S2")
      (value "TL3301AF160QJ")
      (footprint "ButtonE-Switch:TL3301AF160QJ")
      (description "Tactile Switch, DPST; Thru-Hole; Vertical; Rating DC 12V, 50mA (max)")
      (fields (field (name "MANUFACTURER") "E-Switch"))
      (libsource (lib "IL Switch Push Button") (part "IT-2175"))
    )
    (comp (ref "U10")
      (value "CYUSB3014-BZXC")
      (footprint "BGA-121")
      (description "USB Controller")
      (fields (field (name "MANUFACTURER") "Cypress Semiconductor"))
      (libsource (lib "CYUSB3KIT-001 FX3 device symbol (1)_Library") (part "FX3_121_BUMP_4"))
    )
    (comp (ref "U11")
      (value "24LC256-I/SN")
      (footprint "24LC256:SOIC8-N_MC")
      (description "256Kbit, 400kHz, 2.5V, I2C Serial EEPROM, 8-Pin SOIC 150mil, Industrial Temperature")
      (fields (field (name "MANUFACTURER") "Microchip") (field (name "PARTNUMBER") "24LC256T-I/SN"))
      (libsource (lib "Microchip Memory I2C Serial EEPROM") (part "24LC256-I/SN"))
    )
    (comp (ref "Y3")
      (value "NX2520SA-19.200000MHz-NBG1")
      (footprint "NDKCrystals:NX2520SA-19.200000MHz")
      (description "Cristales 19.2000MHz 10ppm 7pF -30C +85C")
      (fields (field (name "MANUFACTURER") "NDK") (field (name "PARTNUMBER") "EXS00A-CS05400"))
      (libsource (lib "FA-20HS") (part "Component_1"))
    )
  )
  (nets
    (net (code "1") (name "/AVDD") (class "Default")
      (node (ref "C168") (pin "2") (pinfunction "2_2") (pintype "passive"))
      (node (ref "C169") (pin "1") (pinfunction "1_1") (pintype "passive"))
      (node (ref "L9") (pin "2") (pinfunction "2_2") (pintype "passive"))
      (node (ref "U10") (pin "A7") (pinfunction "AVDD_A7") (pintype "passive"))
    )
    (net (code "2") (name "/CVDDQ") (class "Default")
      (node (ref "C175") (pin "2") (pinfunction "2_2") (pintype "passive"))
      (node (ref "C176") (pin "2") (pinfunction "2_2") (pintype "passive"))
      (node (ref "L12") (pin "2") (pinfunction "2_2") (pintype "passive"))
      (node (ref "U10") (pin "B6") (pinfunction "CVDDQ_B6") (pintype "passive"))
    )
    (net (code "3") (name "/CapTX_N") (class "Default")
      (node (ref "C178") (pin "2") (pinfunction "2_2") (pintype "passive"))
      (node (ref "U10") (pin "A6") (pinfunction "SSTXM_A6") (pintype "passive"))
    )
    (net (code "4") (name "/CapTX_P") (class "Default")
      (node (ref "C177") (pin "2") (pinfunction "2_2") (pintype "passive"))
      (node (ref "U10") (pin "A5") (pinfunction "SSTXP_A5") (pintype "passive"))
    )
    (net (code "5") (name "/D_N") (class "Default")
      (node (ref "J6") (pin "2") (pinfunction "D-_2") (pintype "passive"))
      (node (ref "U10") (pin "A10") (pinfunction "DM_A10") (pintype "passive"))
    )
    (net (code "6") (name "/D_P") (class "Default")
      (node (ref "J6") (pin "3") (pinfunction "D+_3") (pintype "passive"))
      (node (ref "U10") (pin "A9") (pinfunction "DP_A9") (pintype "passive"))
    )
    (net (code "7") (name "/EsdSSRX_N") (class "Default")
      (node (ref "D4") (pin "1") (pinfunction "I/O1_1") (pintype "passive"))
      (node (ref "U10") (pin "A3") (pinfunction "SSRXM_A3") (pintype "passive"))
    )
    (net (code "8") (name "/EsdSSRX_P") (class "Default")
      (node (ref "D4") (pin "2") (pinfunction "I/O2_2") (pintype "passive"))
      (node (ref "U10") (pin "A4") (pinfunction "SSRXP_A4") (pintype "passive"))
    )
    (net (code "9") (name "/EsdSSTX_N") (class "Default")
      (node (ref "C178") (pin "1") (pinfunction "1_1") (pintype "passive"))
      (node (ref "D4") (pin "5") (pinfunction "I/O4_5") (pintype "passive"))
    )
    (net (code "10") (name "/EsdSSTX_P") (class "Default")
      (node (ref "C177") (pin "1") (pinfunction "1_1") (pintype "passive"))
      (node (ref "D4") (pin "4") (pinfunction "I/O3_4") (pintype "passive"))
    )
    (net (code "11") (name "/FX3_CTL0") (class "Default")
      (node (ref "R62") (pin "1") (pinfunction "1_1") (pintype "passive"))
    )
    (net (code "12") (name "/FX3_CTL1") (class "Default")
      (node (ref "R63") (pin "1") (pinfunction "1_1") (pintype "passive"))
    )
    (net (code "13") (name "/FX3_CTL2") (class "Default")
      (node (ref "R64") (pin "1") (pinfunction "1_1") (pintype "passive"))
    )
    (net (code "14") (name "/FX3_CTL3") (class "Default")
      (node (ref "R65") (pin "1") (pinfunction "1_1") (pintype "passive"))
    )
    (net (code "15") (name "/FX3_CTL4") (class "Default")
      (node (ref "R66") (pin "1") (pinfunction "1_1") (pintype "passive"))
    )
    (net (code "16") (name "/FX3_CTL5") (class "Default")
      (node (ref "R69") (pin "1") (pinfunction "1_1") (pintype "passive"))
    )
    (net (code "17") (name "/FX3_CTL6") (class "Default")
      (node (ref "R73") (pin "1") (pinfunction "1_1") (pintype "passive"))
    )
    (net (code "18") (name "/FX3_CTL7") (class "Default")
      (node (ref "R74") (pin "1") (pinfunction "1_1") (pintype "passive"))
    )
    (net (code "19") (name "/FX3_CTL8") (class "Default")
      (node (ref "R75") (pin "1") (pinfunction "1_1") (pintype "passive"))
    )
    (net (code "20") (name "/FX3_CTL9") (class "Default")
      (node (ref "R76") (pin "1") (pinfunction "1_1") (pintype "passive"))
    )
    (net (code "21") (name "/FX3_CTL10") (class "Default")
      (node (ref "R77") (pin "1") (pinfunction "1_1") (pintype "passive"))
    )
    (net (code "22") (name "/FX3_CTL11") (class "Default")
      (node (ref "R78") (pin "1") (pinfunction "1_1") (pintype "passive"))
    )
    (net (code "23") (name "/FX3_CTL12") (class "Default")
      (node (ref "R79") (pin "1") (pinfunction "1_1") (pintype "passive"))
    )
    (net (code "25") (name "/FX3_DQ0") (class "Default")
      (node (ref "R44") (pin "1") (pinfunction "1_1") (pintype "passive"))
    )
    (net (code "26") (name "/FX3_DQ1") (class "Default")
      (node (ref "R45") (pin "1") (pinfunction "1_1") (pintype "passive"))
    )
    (net (code "27") (name "/FX3_DQ2") (class "Default")
      (node (ref "R46") (pin "1") (pinfunction "1_1") (pintype "passive"))
    )
    (net (code "28") (name "/FX3_DQ3") (class "Default")
      (node (ref "R47") (pin "1") (pinfunction "1_1") (pintype "passive"))
    )
    (net (code "29") (name "/FX3_DQ4") (class "Default")
      (node (ref "R48") (pin "1") (pinfunction "1_1") (pintype "passive"))
    )
    (net (code "30") (name "/FX3_DQ5") (class "Default")
      (node (ref "R50") (pin "1") (pinfunction "1_1") (pintype "passive"))
    )
    (net (code "31") (name "/FX3_DQ6") (class "Default")
      (node (ref "R51") (pin "1") (pinfunction "1_1") (pintype "passive"))
    )
    (net (code "32") (name "/FX3_DQ7") (class "Default")
      (node (ref "R52") (pin "1") (pinfunction "1_1") (pintype "passive"))
    )
    (net (code "33") (name "/FX3_DQ8") (class "Default")
      (node (ref "R53") (pin "1") (pinfunction "1_1") (pintype "passive"))
    )
    (net (code "34") (name "/FX3_DQ9") (class "Default")
      (node (ref "R54") (pin "1") (pinfunction "1_1") (pintype "passive"))
    )
    (net (code "35") (name "/FX3_DQ10") (class "Default")
      (node (ref "R55") (pin "1") (pinfunction "1_1") (pintype "passive"))
    )
    (net (code "36") (name "/FX3_DQ11") (class "Default")
      (node (ref "R56") (pin "1") (pinfunction "1_1") (pintype "passive"))
    )
    (net (code "37") (name "/FX3_DQ12") (class "Default")
      (node (ref "R57") (pin "1") (pinfunction "1_1") (pintype "passive"))
    )
    (net (code "38") (name "/FX3_DQ13") (class "Default")
      (node (ref "R58") (pin "1") (pinfunction "1_1") (pintype "passive"))
    )
    (net (code "39") (name "/FX3_DQ14") (class "Default")
      (node (ref "R59") (pin "1") (pinfunction "1_1") (pintype "passive"))
    )
    (net (code "40") (name "/FX3_DQ15") (class "Default")
      (node (ref "R60") (pin "1") (pinfunction "1_1") (pintype "passive"))
    )
    (net (code "41") (name "/FX3_DQ16") (class "Default")
      (node (ref "R81") (pin "1") (pinfunction "1_1") (pintype "passive"))
    )
    (net (code "42") (name "/FX3_DQ17") (class "Default")
      (node (ref "R82") (pin "1") (pinfunction "1_1") (pintype "passive"))
    )
    (net (code "43") (name "/FX3_DQ18") (class "Default")
      (node (ref "R83") (pin "1") (pinfunction "1_1") (pintype "passive"))
    )
    (net (code "44") (name "/FX3_DQ19") (class "Default")
      (node (ref "R84") (pin "1") (pinfunction "1_1") (pintype "passive"))
    )
    (net (code "45") (name "/FX3_DQ20") (class "Default")
      (node (ref "R85") (pin "1") (pinfunction "1_1") (pintype "passive"))
    )
    (net (code "46") (name "/FX3_DQ21") (class "Default")
      (node (ref "R86") (pin "1") (pinfunction "1_1") (pintype "passive"))
    )
    (net (code "47") (name "/FX3_DQ22") (class "Default")
      (node (ref "R87") (pin "1") (pinfunction "1_1") (pintype "passive"))
    )
    (net (code "48") (name "/FX3_DQ23") (class "Default")
      (node (ref "R88") (pin "1") (pinfunction "1_1") (pintype "passive"))
    )
    (net (code "49") (name "/FX3_DQ24") (class "Default")
      (node (ref "R89") (pin "1") (pinfunction "1_1") (pintype "passive"))
    )
    (net (code "50") (name "/FX3_DQ25") (class "Default")
      (node (ref "R90") (pin "1") (pinfunction "1_1") (pintype "passive"))
    )
    (net (code "51") (name "/FX3_DQ26") (class "Default")
      (node (ref "R91") (pin "1") (pinfunction "1_1") (pintype "passive"))
    )
    (net (code "52") (name "/FX3_DQ27") (class "Default")
      (node (ref "R92") (pin "1") (pinfunction "1_1") (pintype "passive"))
    )
    (net (code "53") (name "/FX3_DQ28") (class "Default")
      (node (ref "R93") (pin "1") (pinfunction "1_1") (pintype "passive"))
    )
    (net (code "54") (name "/FX3_DQ29") (class "Default")
      (node (ref "R94") (pin "1") (pinfunction "1_1") (pintype "passive"))
    )
    (net (code "55") (name "/FX3_DQ30") (class "Default")
      (node (ref "R95") (pin "1") (pinfunction "1_1") (pintype "passive"))
    )
    (net (code "56") (name "/FX3_DQ31") (class "Default")
      (node (ref "R96") (pin "1") (pinfunction "1_1") (pintype "passive"))
    )
    (net (code "58") (name "/FX3_GPIO50") (class "Default")
      (node (ref "U10") (pin "D1") (pinfunction "I2S-CLK_D1") (pintype "passive"))
    )
    (net (code "59") (name "/FX3_GPIO52") (class "Default")
      (node (ref "U10") (pin "D3") (pinfunction "I2S-WS_D3") (pintype "passive"))
    )
    (net (code "60") (name "/FX3_I2C_SCL") (class "Default")
      (node (ref "R71") (pin "1") (pinfunction "1_1") (pintype "passive"))
      (node (ref "U10") (pin "D9") (pinfunction "I2C-GPIO58_SCL_D9") (pintype "passive"))
      (node (ref "U11") (pin "6") (pinfunction "SCL_6") (pintype "input"))
    )
    (net (code "61") (name "/FX3_I2C_SDA") (class "Default")
      (node (ref "R72") (pin "1") (pinfunction "1_1") (pintype "passive"))
      (node (ref "U10") (pin "D10") (pinfunction "I2C-GPIO59_SDA_D10") (pintype "passive"))
      (node (ref "U11") (pin "5") (pinfunction "SDA_5") (pintype "bidirectional"))
    )
    (net (code "62") (name "/FX3_INT_CTL") (class "Default")
      (node (ref "U10") (pin "L8") (pinfunction "INT_N_CTL15_L8") (pintype "passive"))
    )
    (net (code "63") (name "/FX3_JTAG_TCK") (class "Default")
      (node (ref "P10") (pin "3") (pinfunction "3_3") (pintype "passive"))
      (node (ref "U10") (pin "F6") (pinfunction "TCK_F6") (pintype "passive"))
    )
    (net (code "64") (name "/FX3_JTAG_TDI") (class "Default")
      (node (ref "P10") (pin "7") (pinfunction "7_7") (pintype "passive"))
      (node (ref "U10") (pin "E7") (pinfunction "TDI_E7") (pintype "passive"))
    )
    (net (code "65") (name "/FX3_JTAG_TDO") (class "Default")
      (node (ref "P10") (pin "9") (pinfunction "9_9") (pintype "passive"))
      (node (ref "U10") (pin "C10") (pinfunction "TDO_C10") (pintype "passive"))
    )
    (net (code "66") (name "/FX3_JTAG_TMS") (class "Default")
      (node (ref "P10") (pin "5") (pinfunction "5_5") (pintype "passive"))
      (node (ref "U10") (pin "E8") (pinfunction "TMS_E8") (pintype "passive"))
    )
    (net (code "67") (name "/FX3_JTAG_TRST_N") (class "Default")
      (node (ref "P10") (pin "1") (pinfunction "1_1") (pintype "passive"))
      (node (ref "U10") (pin "B11") (pinfunction "TRST_N_B11") (pintype "passive"))
    )
    (net (code "68") (name "/FX3_PCLK") (class "Default")
      (node (ref "R61") (pin "1") (pinfunction "1_1") (pintype "passive"))
    )
    (net (code "69") (name "/FX3_RESET") (class "Default")
      (node (ref "C172") (pin "2") (pinfunction "2_2") (pintype "passive"))
      (node (ref "R80") (pin "2") (pinfunction "2_2") (pintype "passive"))
      (node (ref "S2") (pin "1") (pinfunction "1_1") (pintype "passive"))
      (node (ref "S2") (pin "2") (pinfunction "2_2") (pintype "passive"))
      (node (ref "U10") (pin "C5") (pinfunction "RESET_N_C5") (pintype "passive"))
    )
    (net (code "70") (name "/FX3_R_USB2") (class "Default")
      (node (ref "R98") (pin "2") (pinfunction "2_2") (pintype "passive"))
      (node (ref "U10") (pin "C8") (pinfunction "R_USB2_C8") (pintype "passive"))
    )
    (net (code "71") (name "/FX3_R_USB3") (class "Default")
      (node (ref "R99") (pin "2") (pinfunction "2_2") (pintype "passive"))
      (node (ref "U10") (pin "B3") (pinfunction "R_USB3_B3") (pintype "passive"))
    )
    (net (code "72") (name "/FX3_SPI_CLOCK") (class "Default")
      (node (ref "U10") (pin "D4") (pinfunction "UART-RTS_SPI-SCK_D4") (pintype "passive"))
    )
    (net (code "73") (name "/FX3_SPI_MISO") (class "Default")
      (node (ref "U10") (pin "C2") (pinfunction "UART-TX_SPI-MISO_C2") (pintype "passive"))
    )
    (net (code "74") (name "/FX3_SPI_MOSI") (class "Default")
      (node (ref "U10") (pin "D5") (pinfunction "UART-RX_SPI-MOSI_D5") (pintype "passive"))
    )
    (net (code "75") (name "/FX3_SPI_SSN") (class "Default")
      (node (ref "U10") (pin "C1") (pinfunction "UART-CTS_SPI-SSN_C1") (pintype "passive"))
    )
    (net (code "76") (name "/OTG_ID") (class "Default")
      (node (ref "J6") (pin "4") (pinfunction "ID_4") (pintype "passive"))
      (node (ref "U10") (pin "C9") (pinfunction "OTG_ID_C9") (pintype "passive"))
    )
    (net (code "77") (name "/R_CTL0") (class "Default")
      (node (ref "R62") (pin "2") (pinfunction "2_2") (pintype "passive"))
      (node (ref "U10") (pin "K8") (pinfunction "CTL0_K8") (pintype "passive"))
    )
    (net (code "78") (name "/R_CTL1") (class "Default")
      (node (ref "R63") (pin "2") (pinfunction "2_2") (pintype "passive"))
      (node (ref "U10") (pin "K7") (pinfunction "CTL1_K7") (pintype "passive"))
    )
    (net (code "79") (name "/R_CTL2") (class "Default")
      (node (ref "R64") (pin "2") (pinfunction "2_2") (pintype "passive"))
      (node (ref "U10") (pin "J7") (pinfunction "CTL2_J7") (pintype "passive"))
    )
    (net (code "80") (name "/R_CTL3") (class "Default")
      (node (ref "R65") (pin "2") (pinfunction "2_2") (pintype "passive"))
      (node (ref "U10") (pin "H7") (pinfunction "CTL3_H7") (pintype "passive"))
    )
    (net (code "81") (name "/R_CTL4") (class "Default")
      (node (ref "R66") (pin "2") (pinfunction "2_2") (pintype "passive"))
      (node (ref "U10") (pin "G7") (pinfunction "CTL4_G7") (pintype "passive"))
    )
    (net (code "82") (name "/R_CTL5") (class "Default")
      (node (ref "R69") (pin "2") (pinfunction "2_2") (pintype "passive"))
      (node (ref "U10") (pin "G6") (pinfunction "CTL5_G6") (pintype "passive"))
    )
    (net (code "83") (name "/R_CTL6") (class "Default")
      (node (ref "R73") (pin "2") (pinfunction "2_2") (pintype "passive"))
      (node (ref "U10") (pin "K6") (pinfunction "CTL6_K6") (pintype "passive"))
    )
    (net (code "84") (name "/R_CTL7") (class "Default")
      (node (ref "R74") (pin "2") (pinfunction "2_2") (pintype "passive"))
      (node (ref "U10") (pin "H8") (pinfunction "CTL7_H8") (pintype "passive"))
    )
    (net (code "85") (name "/R_CTL8") (class "Default")
      (node (ref "R75") (pin "2") (pinfunction "2_2") (pintype "passive"))
      (node (ref "U10") (pin "G5") (pinfunction "CTL8_G5") (pintype "passive"))
    )
    (net (code "86") (name "/R_CTL9") (class "Default")
      (node (ref "R76") (pin "2") (pinfunction "2_2") (pintype "passive"))
      (node (ref "U10") (pin "H6") (pinfunction "CTL9_H6") (pintype "passive"))
    )
    (net (code "87") (name "/R_CTL10") (class "Default")
      (node (ref "R77") (pin "2") (pinfunction "2_2") (pintype "passive"))
      (node (ref "U10") (pin "K5") (pinfunction "CTL10_K5") (pintype "passive"))
    )
    (net (code "88") (name "/R_CTL11") (class "Default")
      (node (ref "R78") (pin "2") (pinfunction "2_2") (pintype "passive"))
      (node (ref "U10") (pin "J5") (pinfunction "CTL11_J5") (pintype "passive"))
    )
    (net (code "89") (name "/R_CTL12") (class "Default")
      (node (ref "R79") (pin "2") (pinfunction "2_2") (pintype "passive"))
      (node (ref "U10") (pin "H5") (pinfunction "CTL12_H5") (pintype "passive"))
    )
    (net (code "90") (name "/R_DQ0") (class "Default")
      (node (ref "R44") (pin "2") (pinfunction "2_2") (pintype "passive"))
      (node (ref "U10") (pin "F10") (pinfunction "DQ0_F10") (pintype "passive"))
    )
    (net (code "91") (name "/R_DQ1") (class "Default")
      (node (ref "R45") (pin "2") (pinfunction "2_2") (pintype "passive"))
      (node (ref "U10") (pin "F9") (pinfunction "DQ1_F9") (pintype "passive"))
    )
    (net (code "92") (name "/R_DQ2") (class "Default")
      (node (ref "R46") (pin "2") (pinfunction "2_2") (pintype "passive"))
      (node (ref "U10") (pin "F7") (pinfunction "DQ2_F7") (pintype "passive"))
    )
    (net (code "93") (name "/R_DQ3") (class "Default")
      (node (ref "R47") (pin "2") (pinfunction "2_2") (pintype "passive"))
      (node (ref "U10") (pin "G10") (pinfunction "DQ3_G10") (pintype "passive"))
    )
    (net (code "94") (name "/R_DQ4") (class "Default")
      (node (ref "R48") (pin "2") (pinfunction "2_2") (pintype "passive"))
      (node (ref "U10") (pin "G9") (pinfunction "DQ4_G9") (pintype "passive"))
    )
    (net (code "95") (name "/R_DQ5") (class "Default")
      (node (ref "R50") (pin "2") (pinfunction "2_2") (pintype "passive"))
      (node (ref "U10") (pin "F8") (pinfunction "DQ5_F8") (pintype "passive"))
    )
    (net (code "96") (name "/R_DQ6") (class "Default")
      (node (ref "R51") (pin "2") (pinfunction "2_2") (pintype "passive"))
      (node (ref "U10") (pin "H10") (pinfunction "DQ6_H10") (pintype "passive"))
    )
    (net (code "97") (name "/R_DQ7") (class "Default")
      (node (ref "R52") (pin "2") (pinfunction "2_2") (pintype "passive"))
      (node (ref "U10") (pin "H9") (pinfunction "DQ7_H9") (pintype "passive"))
    )
    (net (code "98") (name "/R_DQ8") (class "Default")
      (node (ref "R53") (pin "2") (pinfunction "2_2") (pintype "passive"))
      (node (ref "U10") (pin "J10") (pinfunction "DQ8_J10") (pintype "passive"))
    )
    (net (code "99") (name "/R_DQ9") (class "Default")
      (node (ref "R54") (pin "2") (pinfunction "2_2") (pintype "passive"))
      (node (ref "U10") (pin "J9") (pinfunction "DQ9_J9") (pintype "passive"))
    )
    (net (code "100") (name "/R_DQ10") (class "Default")
      (node (ref "R55") (pin "2") (pinfunction "2_2") (pintype "passive"))
      (node (ref "U10") (pin "K11") (pinfunction "DQ10_K11") (pintype "passive"))
    )
    (net (code "101") (name "/R_DQ11") (class "Default")
      (node (ref "R56") (pin "2") (pinfunction "2_2") (pintype "passive"))
      (node (ref "U10") (pin "L10") (pinfunction "DQ11_L10") (pintype "passive"))
    )
    (net (code "102") (name "/R_DQ12") (class "Default")
      (node (ref "R57") (pin "2") (pinfunction "2_2") (pintype "passive"))
      (node (ref "U10") (pin "K10") (pinfunction "DQ12_K10") (pintype "passive"))
    )
    (net (code "103") (name "/R_DQ13") (class "Default")
      (node (ref "R58") (pin "2") (pinfunction "2_2") (pintype "passive"))
      (node (ref "U10") (pin "K9") (pinfunction "DQ13_K9") (pintype "passive"))
    )
    (net (code "104") (name "/R_DQ14") (class "Default")
      (node (ref "R59") (pin "2") (pinfunction "2_2") (pintype "passive"))
      (node (ref "U10") (pin "J8") (pinfunction "DQ14_J8") (pintype "passive"))
    )
    (net (code "105") (name "/R_DQ15") (class "Default")
      (node (ref "R60") (pin "2") (pinfunction "2_2") (pintype "passive"))
      (node (ref "U10") (pin "G8") (pinfunction "DQ15_G8") (pintype "passive"))
    )
    (net (code "106") (name "/R_DQ16") (class "Default")
      (node (ref "R81") (pin "2") (pinfunction "2_2") (pintype "passive"))
      (node (ref "U10") (pin "K2") (pinfunction "DQ16_K2") (pintype "passive"))
    )
    (net (code "107") (name "/R_DQ17") (class "Default")
      (node (ref "R82") (pin "2") (pinfunction "2_2") (pintype "passive"))
      (node (ref "U10") (pin "J4") (pinfunction "DQ17_J4") (pintype "passive"))
    )
    (net (code "108") (name "/R_DQ18") (class "Default")
      (node (ref "R83") (pin "2") (pinfunction "2_2") (pintype "passive"))
      (node (ref "U10") (pin "K1") (pinfunction "DQ18_K1") (pintype "passive"))
    )
    (net (code "109") (name "/R_DQ19") (class "Default")
      (node (ref "R84") (pin "2") (pinfunction "2_2") (pintype "passive"))
      (node (ref "U10") (pin "J2") (pinfunction "DQ19_J2") (pintype "passive"))
    )
    (net (code "110") (name "/R_DQ20") (class "Default")
      (node (ref "R85") (pin "2") (pinfunction "2_2") (pintype "passive"))
      (node (ref "U10") (pin "J3") (pinfunction "DQ20_J3") (pintype "passive"))
    )
    (net (code "111") (name "/R_DQ21") (class "Default")
      (node (ref "R86") (pin "2") (pinfunction "2_2") (pintype "passive"))
      (node (ref "U10") (pin "J1") (pinfunction "DQ21_J1") (pintype "passive"))
    )
    (net (code "112") (name "/R_DQ22") (class "Default")
      (node (ref "R87") (pin "2") (pinfunction "2_2") (pintype "passive"))
      (node (ref "U10") (pin "H2") (pinfunction "DQ22_H2") (pintype "passive"))
    )
    (net (code "113") (name "/R_DQ23") (class "Default")
      (node (ref "R88") (pin "2") (pinfunction "2_2") (pintype "passive"))
      (node (ref "U10") (pin "H3") (pinfunction "DQ23_H3") (pintype "passive"))
    )
    (net (code "114") (name "/R_DQ24") (class "Default")
      (node (ref "R89") (pin "2") (pinfunction "2_2") (pintype "passive"))
      (node (ref "U10") (pin "F4") (pinfunction "DQ24_F4") (pintype "passive"))
    )
    (net (code "115") (name "/R_DQ25") (class "Default")
      (node (ref "R90") (pin "2") (pinfunction "2_2") (pintype "passive"))
      (node (ref "U10") (pin "G2") (pinfunction "DQ25_G2") (pintype "passive"))
    )
    (net (code "116") (name "/R_DQ26") (class "Default")
      (node (ref "R91") (pin "2") (pinfunction "2_2") (pintype "passive"))
      (node (ref "U10") (pin "G3") (pinfunction "DQ26_G3") (pintype "passive"))
    )
    (net (code "117") (name "/R_DQ27") (class "Default")
      (node (ref "R92") (pin "2") (pinfunction "2_2") (pintype "passive"))
      (node (ref "U10") (pin "F3") (pinfunction "DQ27_F3") (pintype "passive"))
    )
    (net (code "118") (name "/R_DQ28") (class "Default")
      (node (ref "R93") (pin "2") (pinfunction "2_2") (pintype "passive"))
      (node (ref "U10") (pin "F5") (pinfunction "DQ28_F5") (pintype "passive"))
    )
    (net (code "119") (name "/R_DQ29") (class "Default")
      (node (ref "R94") (pin "2") (pinfunction "2_2") (pintype "passive"))
      (node (ref "U10") (pin "E1") (pinfunction "DQ29_E1") (pintype "passive"))
    )
    (net (code "120") (name "/R_DQ30") (class "Default")
      (node (ref "R95") (pin "2") (pinfunction "2_2") (pintype "passive"))
      (node (ref "U10") (pin "E5") (pinfunction "DQ30_E5") (pintype "passive"))
    )
    (net (code "121") (name "/R_DQ31") (class "Default")
      (node (ref "R96") (pin "2") (pinfunction "2_2") (pintype "passive"))
      (node (ref "U10") (pin "E4") (pinfunction "DQ31_E4") (pintype "passive"))
    )
    (net (code "122") (name "/R_PCLK") (class "Default")
      (node (ref "R61") (pin "2") (pinfunction "2_2") (pintype "passive"))
      (node (ref "U10") (pin "J6") (pinfunction "PCLK_J6") (pintype "passive"))
    )
    (net (code "123") (name "/SSRX_N") (class "Default")
      (node (ref "D4") (pin "10") (pinfunction "NC_10") (pintype "passive"))
      (node (ref "J6") (pin "10") (pinfunction "MicB_SSRX+_10") (pintype "passive"))
    )
    (net (code "124") (name "/SSRX_P") (class "Default")
      (node (ref "D4") (pin "9") (pinfunction "NC_9") (pintype "passive"))
      (node (ref "J6") (pin "9") (pinfunction "MicB_SSRX-_9") (pintype "passive"))
    )
    (net (code "125") (name "/SSTX_N") (class "Default")
      (node (ref "D4") (pin "6") (pinfunction "NC_6") (pintype "passive"))
      (node (ref "J6") (pin "6") (pinfunction "MicB_SSTX-_6") (pintype "passive"))
    )
    (net (code "126") (name "/SSTX_P") (class "Default")
      (node (ref "D4") (pin "7") (pinfunction "NC_7") (pintype "passive"))
      (node (ref "J6") (pin "7") (pinfunction "MicB_SSTX+_7") (pintype "passive"))
    )
    (net (code "127") (name "/U3RXVDDQ") (class "Default")
      (node (ref "C170") (pin "2") (pinfunction "2_2") (pintype "passive"))
      (node (ref "C171") (pin "1") (pinfunction "1_1") (pintype "passive"))
      (node (ref "L10") (pin "2") (pinfunction "2_2") (pintype "passive"))
      (node (ref "U10") (pin "A2") (pinfunction "U3RXVDDQ_A2") (pintype "passive"))
    )
    (net (code "128") (name "/U3TXVDDQ") (class "Default")
      (node (ref "C173") (pin "2") (pinfunction "2_2") (pintype "passive"))
      (node (ref "C174") (pin "1") (pinfunction "1_1") (pintype "passive"))
      (node (ref "L11") (pin "2") (pinfunction "2_2") (pintype "passive"))
      (node (ref "U10") (pin "B5") (pinfunction "U3TXVDDQ_B5") (pintype "passive"))
    )
    (net (code "129") (name "/XTALIN") (class "Default")
      (node (ref "C144") (pin "1") (pinfunction "1_1") (pintype "passive"))
      (node (ref "U10") (pin "C6") (pinfunction "XTALIN_C6") (pintype "passive"))
      (node (ref "Y3") (pin "1") (pintype "passive"))
    )
    (net (code "130") (name "/XTALOUT") (class "Default")
      (node (ref "C145") (pin "1") (pinfunction "1_1") (pintype "passive"))
      (node (ref "U10") (pin "C7") (pinfunction "XTALOUT_C7") (pintype "passive"))
      (node (ref "Y3") (pin "3") (pintype "passive"))
    )
    (net (code "131") (name "1.2V") (class "Default")
      (node (ref "P8") (pin "1") (pinfunction "1_1") (pintype "passive"))
    )
    (net (code "132") (name "1.2V_USB") (class "Default")
      (node (ref "C146") (pin "2") (pinfunction "2_2") (pintype "passive"))
      (node (ref "C147") (pin "2") (pinfunction "2_2") (pintype "passive"))
      (node (ref "C148") (pin "2") (pinfunction "2_2") (pintype "passive"))
      (node (ref "C149") (pin "2") (pinfunction "2_2") (pintype "passive"))
      (node (ref "C150") (pin "2") (pinfunction "2_2") (pintype "passive"))
      (node (ref "C151") (pin "2") (pinfunction "2_2") (pintype "passive"))
      (node (ref "C152") (pin "2") (pinfunction "2_2") (pintype "passive"))
      (node (ref "C153") (pin "2") (pinfunction "2_2") (pintype "passive"))
      (node (ref "C154") (pin "1") (pinfunction "1_1") (pintype "passive"))
      (node (ref "C155") (pin "2") (pinfunction "2_2") (pintype "passive"))
      (node (ref "C156") (pin "2") (pinfunction "2_2") (pintype "passive"))
      (node (ref "L10") (pin "1") (pinfunction "1_1") (pintype "passive"))
      (node (ref "L11") (pin "1") (pinfunction "1_1") (pintype "passive"))
      (node (ref "L9") (pin "1") (pinfunction "1_1") (pintype "passive"))
      (node (ref "P8") (pin "2") (pinfunction "2_2") (pintype "passive"))
      (node (ref "U10") (pin "B10") (pinfunction "VDD_EFVDDQ_B10") (pintype "passive"))
      (node (ref "U10") (pin "C3") (pinfunction "VDD2_C3") (pintype "passive"))
      (node (ref "U10") (pin "E9") (pinfunction "VDD4_E9") (pintype "passive"))
      (node (ref "U10") (pin "F11") (pinfunction "VDD5_F11") (pintype "passive"))
      (node (ref "U10") (pin "H1") (pinfunction "VDD1_H1") (pintype "passive"))
      (node (ref "U10") (pin "J11") (pinfunction "VDD_SRAM_VDD2_J11") (pintype "passive"))
      (node (ref "U10") (pin "L5") (pinfunction "VDD_SRAM_VDD1_L5") (pintype "passive"))
      (node (ref "U10") (pin "L7") (pinfunction "VDD3_L7") (pintype "passive"))
    )
    (net (code "133") (name "1.8V") (class "Default")
      (node (ref "P9") (pin "1") (pinfunction "1_1") (pintype "passive"))
    )
    (net (code "134") (name "1.8V_USB") (class "Default")
      (node (ref "C157") (pin "2") (pinfunction "2_2") (pintype "passive"))
      (node (ref "C158") (pin "2") (pinfunction "2_2") (pintype "passive"))
      (node (ref "C159") (pin "2") (pinfunction "2_2") (pintype "passive"))
      (node (ref "C160") (pin "2") (pinfunction "2_2") (pintype "passive"))
      (node (ref "C161") (pin "2") (pinfunction "2_2") (pintype "passive"))
      (node (ref "C162") (pin "2") (pinfunction "2_2") (pintype "passive"))
      (node (ref "C163") (pin "2") (pinfunction "2_2") (pintype "passive"))
      (node (ref "C164") (pin "2") (pinfunction "2_2") (pintype "passive"))
      (node (ref "C165") (pin "2") (pinfunction "2_2") (pintype "passive"))
      (node (ref "C166") (pin "2") (pinfunction "2_2") (pintype "passive"))
      (node (ref "C167") (pin "2") (pinfunction "2_2") (pintype "passive"))
      (node (ref "L12") (pin "1") (pinfunction "1_1") (pintype "passive"))
      (node (ref "P10") (pin "11") (pinfunction "11_11") (pintype "passive"))
      (node (ref "P9") (pin "2") (pinfunction "2_2") (pintype "passive"))
      (node (ref "R71") (pin "2") (pinfunction "2_2") (pintype "passive"))
      (node (ref "R72") (pin "2") (pinfunction "2_2") (pintype "passive"))
      (node (ref "R80") (pin "1") (pinfunction "1_1") (pintype "passive"))
      (node (ref "U10") (pin "B1") (pinfunction "VIO4_B1") (pintype "passive"))
      (node (ref "U10") (pin "C11") (pinfunction "VIO5_C11") (pintype "passive"))
      (node (ref "U10") (pin "E3") (pinfunction "VIO3_E3") (pintype "passive"))
      (node (ref "U10") (pin "F1") (pinfunction "VIO2_F1") (pintype "passive"))
      (node (ref "U10") (pin "H11") (pinfunction "VIO1_2_H11") (pintype "passive"))
      (node (ref "U10") (pin "H4") (pinfunction "PMODE1_H4") (pintype "passive"))
      (node (ref "U10") (pin "L9") (pinfunction "VIO1_1_L9") (pintype "passive"))
      (node (ref "U11") (pin "8") (pinfunction "VCC_8") (pintype "power_in"))
    )
    (net (code "135") (name "GND") (class "Default")
      (node (ref "C144") (pin "2") (pinfunction "2_2") (pintype "passive"))
      (node (ref "C145") (pin "2") (pinfunction "2_2") (pintype "passive"))
      (node (ref "C146") (pin "1") (pinfunction "1_1") (pintype "passive"))
      (node (ref "C147") (pin "1") (pinfunction "1_1") (pintype "passive"))
      (node (ref "C148") (pin "1") (pinfunction "1_1") (pintype "passive"))
      (node (ref "C149") (pin "1") (pinfunction "1_1") (pintype "passive"))
      (node (ref "C150") (pin "1") (pinfunction "1_1") (pintype "passive"))
      (node (ref "C151") (pin "1") (pinfunction "1_1") (pintype "passive"))
      (node (ref "C152") (pin "1") (pinfunction "1_1") (pintype "passive"))
      (node (ref "C153") (pin "1") (pinfunction "1_1") (pintype "passive"))
      (node (ref "C154") (pin "2") (pinfunction "2_2") (pintype "passive"))
      (node (ref "C155") (pin "1") (pinfunction "1_1") (pintype "passive"))
      (node (ref "C156") (pin "1") (pinfunction "1_1") (pintype "passive"))
      (node (ref "C157") (pin "1") (pinfunction "1_1") (pintype "passive"))
      (node (ref "C158") (pin "1") (pinfunction "1_1") (pintype "passive"))
      (node (ref "C159") (pin "1") (pinfunction "1_1") (pintype "passive"))
      (node (ref "C160") (pin "1") (pinfunction "1_1") (pintype "passive"))
      (node (ref "C161") (pin "1") (pinfunction "1_1") (pintype "passive"))
      (node (ref "C162") (pin "1") (pinfunction "1_1") (pintype "passive"))
      (node (ref "C163") (pin "1") (pinfunction "1_1") (pintype "passive"))
      (node (ref "C164") (pin "1") (pinfunction "1_1") (pintype "passive"))
      (node (ref "C165") (pin "1") (pinfunction "1_1") (pintype "passive"))
      (node (ref "C166") (pin "1") (pinfunction "1_1") (pintype "passive"))
      (node (ref "C167") (pin "1") (pinfunction "1_1") (pintype "passive"))
      (node (ref "C168") (pin "1") (pinfunction "1_1") (pintype "passive"))
      (node (ref "C169") (pin "2") (pinfunction "2_2") (pintype "passive"))
      (node (ref "C170") (pin "1") (pinfunction "1_1") (pintype "passive"))
      (node (ref "C171") (pin "2") (pinfunction "2_2") (pintype "passive"))
      (node (ref "C172") (pin "1") (pinfunction "1_1") (pintype "passive"))
      (node (ref "C173") (pin "1") (pinfunction "1_1") (pintype "passive"))
      (node (ref "C174") (pin "2") (pinfunction "2_2") (pintype "passive"))
      (node (ref "C175") (pin "1") (pinfunction "1_1") (pintype "passive"))
      (node (ref "C176") (pin "1") (pinfunction "1_1") (pintype "passive"))
      (node (ref "C179") (pin "1") (pinfunction "1_1") (pintype "passive"))
      (node (ref "C180") (pin "2") (pinfunction "2_2") (pintype "passive"))
      (node (ref "D4") (pin "3") (pinfunction "VDD_3") (pintype "passive"))
      (node (ref "D4") (pin "8") (pinfunction "GND_8") (pintype "passive"))
      (node (ref "J6") (pin "5") (pinfunction "GND_5") (pintype "passive"))
      (node (ref "J6") (pin "8") (pinfunction "GND_DRAIN_8") (pintype "passive"))
      (node (ref "L14") (pin "2") (pinfunction "2_2") (pintype "passive"))
      (node (ref "P10") (pin "10") (pinfunction "10_10") (pintype "passive"))
      (node (ref "P10") (pin "12") (pinfunction "12_12") (pintype "passive"))
      (node (ref "P10") (pin "2") (pinfunction "2_2") (pintype "passive"))
      (node (ref "P10") (pin "4") (pinfunction "4_4") (pintype "passive"))
      (node (ref "P10") (pin "6") (pinfunction "6_6") (pintype "passive"))
      (node (ref "P10") (pin "8") (pinfunction "8_8") (pintype "passive"))
      (node (ref "R49") (pin "2") (pinfunction "2_2") (pintype "passive"))
      (node (ref "R67") (pin "1") (pinfunction "1_1") (pintype "passive"))
      (node (ref "R68") (pin "1") (pinfunction "1_1") (pintype "passive"))
      (node (ref "R70") (pin "1") (pinfunction "1_1") (pintype "passive"))
      (node (ref "R98") (pin "1") (pinfunction "1_1") (pintype "passive"))
      (node (ref "R99") (pin "1") (pinfunction "1_1") (pintype "passive"))
      (node (ref "S2") (pin "3") (pinfunction "3_3") (pintype "passive"))
      (node (ref "S2") (pin "4") (pinfunction "4_4") (pintype "passive"))
      (node (ref "U10") (pin "A1") (pinfunction "U3VSSQ_A1") (pintype "passive"))
      (node (ref "U10") (pin "A8") (pinfunction "VSS12_A8") (pintype "passive"))
      (node (ref "U10") (pin "B7") (pinfunction "AVSS_B7") (pintype "passive"))
      (node (ref "U10") (pin "B8") (pinfunction "U2PLLVSSQ_B8") (pintype "passive"))
      (node (ref "U10") (pin "B9") (pinfunction "U2AFEVSSQ_B9") (pintype "passive"))
      (node (ref "U10") (pin "D8") (pinfunction "VSS5_D8") (pintype "passive"))
      (node (ref "U10") (pin "E2") (pinfunction "VSS3_E2") (pintype "passive"))
      (node (ref "U10") (pin "G1") (pinfunction "VSS1_G1") (pintype "passive"))
      (node (ref "U10") (pin "G11") (pinfunction "VSS6_G11") (pintype "passive"))
      (node (ref "U10") (pin "K3") (pinfunction "VSS10_K3") (pintype "passive"))
      (node (ref "U10") (pin "K4") (pinfunction "VSS8_K4") (pintype "passive"))
      (node (ref "U10") (pin "L1") (pinfunction "VSS2_L1") (pintype "passive"))
      (node (ref "U10") (pin "L11") (pinfunction "VSS7_L11") (pintype "passive"))
      (node (ref "U10") (pin "L2") (pinfunction "VSS11_L2") (pintype "passive"))
      (node (ref "U10") (pin "L3") (pinfunction "VSS9_L3") (pintype "passive"))
      (node (ref "U10") (pin "L6") (pinfunction "VSS4_L6") (pintype "passive"))
      (node (ref "U11") (pin "4") (pinfunction "VSS_4") (pintype "power_in"))
      (node (ref "U11") (pin "7") (pinfunction "WP_7") (pintype "input"))
      (node (ref "Y3") (pin "2") (pinfunction "GND_2") (pintype "passive"))
      (node (ref "Y3") (pin "4") (pinfunction "GND_4") (pintype "passive"))
    )
    (net (code "136") (name "Net-(J6-Shield)") (class "Default")
      (node (ref "C179") (pin "2") (pinfunction "2_2") (pintype "passive"))
      (node (ref "J6") (pin "Shell") (pinfunction "Shield_Shell") (pintype "passive"))
      (node (ref "L14") (pin "1") (pinfunction "1_1") (pintype "passive"))
    )
    (net (code "137") (name "Net-(J6-VBUS)") (class "Default")
      (node (ref "J6") (pin "1") (pinfunction "VBUS_1") (pintype "passive"))
      (node (ref "L13") (pin "2") (pinfunction "2_2") (pintype "passive"))
    )
    (net (code "138") (name "Net-(U10E-FSLC0)") (class "Default")
      (node (ref "R49") (pin "1") (pinfunction "1_1") (pintype "passive"))
      (node (ref "U10") (pin "B2") (pinfunction "FSLC0_B2") (pintype "passive"))
      (node (ref "U10") (pin "B4") (pinfunction "FSLC1_B4") (pintype "passive"))
      (node (ref "U10") (pin "E6") (pinfunction "FSLC2_E6") (pintype "passive"))
    )
    (net (code "139") (name "Net-(U11-A0)") (class "Default")
      (node (ref "R67") (pin "2") (pinfunction "2_2") (pintype "passive"))
      (node (ref "U11") (pin "1") (pinfunction "A0_1") (pintype "input"))
    )
    (net (code "140") (name "Net-(U11-A1)") (class "Default")
      (node (ref "R68") (pin "2") (pinfunction "2_2") (pintype "passive"))
      (node (ref "U11") (pin "2") (pinfunction "A1_2") (pintype "input"))
    )
    (net (code "141") (name "Net-(U11-A2)") (class "Default")
      (node (ref "R70") (pin "2") (pinfunction "2_2") (pintype "passive"))
      (node (ref "U11") (pin "3") (pinfunction "A2_3") (pintype "input"))
    )
    (net (code "142") (name "VBUS") (class "Default")
      (node (ref "C180") (pin "1") (pinfunction "1_1") (pintype "passive"))
      (node (ref "L13") (pin "1") (pinfunction "1_1") (pintype "passive"))
      (node (ref "U10") (pin "E11") (pinfunction "VBUS_E11") (pintype "passive"))
    )
    (net (code "143") (name "unconnected-(U10A-PMODE0-PadG4)") (class "Default")
      (node (ref "U10") (pin "G4") (pinfunction "PMODE0_G4") (pintype "passive+no_connect"))
    )
    (net (code "144") (name "unconnected-(U10A-PMODE2-PadL4)") (class "Default")
      (node (ref "U10") (pin "L4") (pinfunction "PMODE2_L4") (pintype "passive+no_connect"))
    )
    (net (code "145") (name "unconnected-(U10B-GPIO45-PadF2)") (class "Default")
      (node (ref "U10") (pin "F2") (pinfunction "GPIO45_F2") (pintype "passive+no_connect"))
    )
    (net (code "146") (name "unconnected-(U10C-I2S-MCLK-PadC4)") (class "Default")
      (node (ref "U10") (pin "C4") (pinfunction "I2S-MCLK_C4") (pintype "passive+no_connect"))
    )
    (net (code "147") (name "unconnected-(U10C-I2S-SD-PadD2)") (class "Default")
      (node (ref "U10") (pin "D2") (pinfunction "I2S-SD_D2") (pintype "passive+no_connect"))
    )
    (net (code "148") (name "unconnected-(U10D-NC-PadA11)") (class "Default")
      (node (ref "U10") (pin "A11") (pinfunction "NC_A11") (pintype "passive+no_connect"))
    )
    (net (code "149") (name "unconnected-(U10E-CLKIN-PadD7)") (class "Default")
      (node (ref "U10") (pin "D7") (pinfunction "CLKIN_D7") (pintype "passive+no_connect"))
    )
    (net (code "150") (name "unconnected-(U10E-CLKIN_32-PadD6)") (class "Default")
      (node (ref "U10") (pin "D6") (pinfunction "CLKIN_32_D6") (pintype "passive+no_connect"))
    )
    (net (code "151") (name "unconnected-(U10F-I2C-GPIO60_CHARGER-DETECT-PadD11)") (class "Default")
      (node (ref "U10") (pin "D11") (pinfunction "I2C-GPIO60_CHARGER-DETECT_D11") (pintype "passive+no_connect"))
    )
    (net (code "152") (name "unconnected-(U10G-VBAT-PadE10)") (class "Default")
      (node (ref "U10") (pin "E10") (pinfunction "VBAT_E10") (pintype "passive+no_connect"))
    )
  )
)
